# trig3_board_de0-nano_lvds.net
KiCad netlist of a schematic drawn in EAGLE
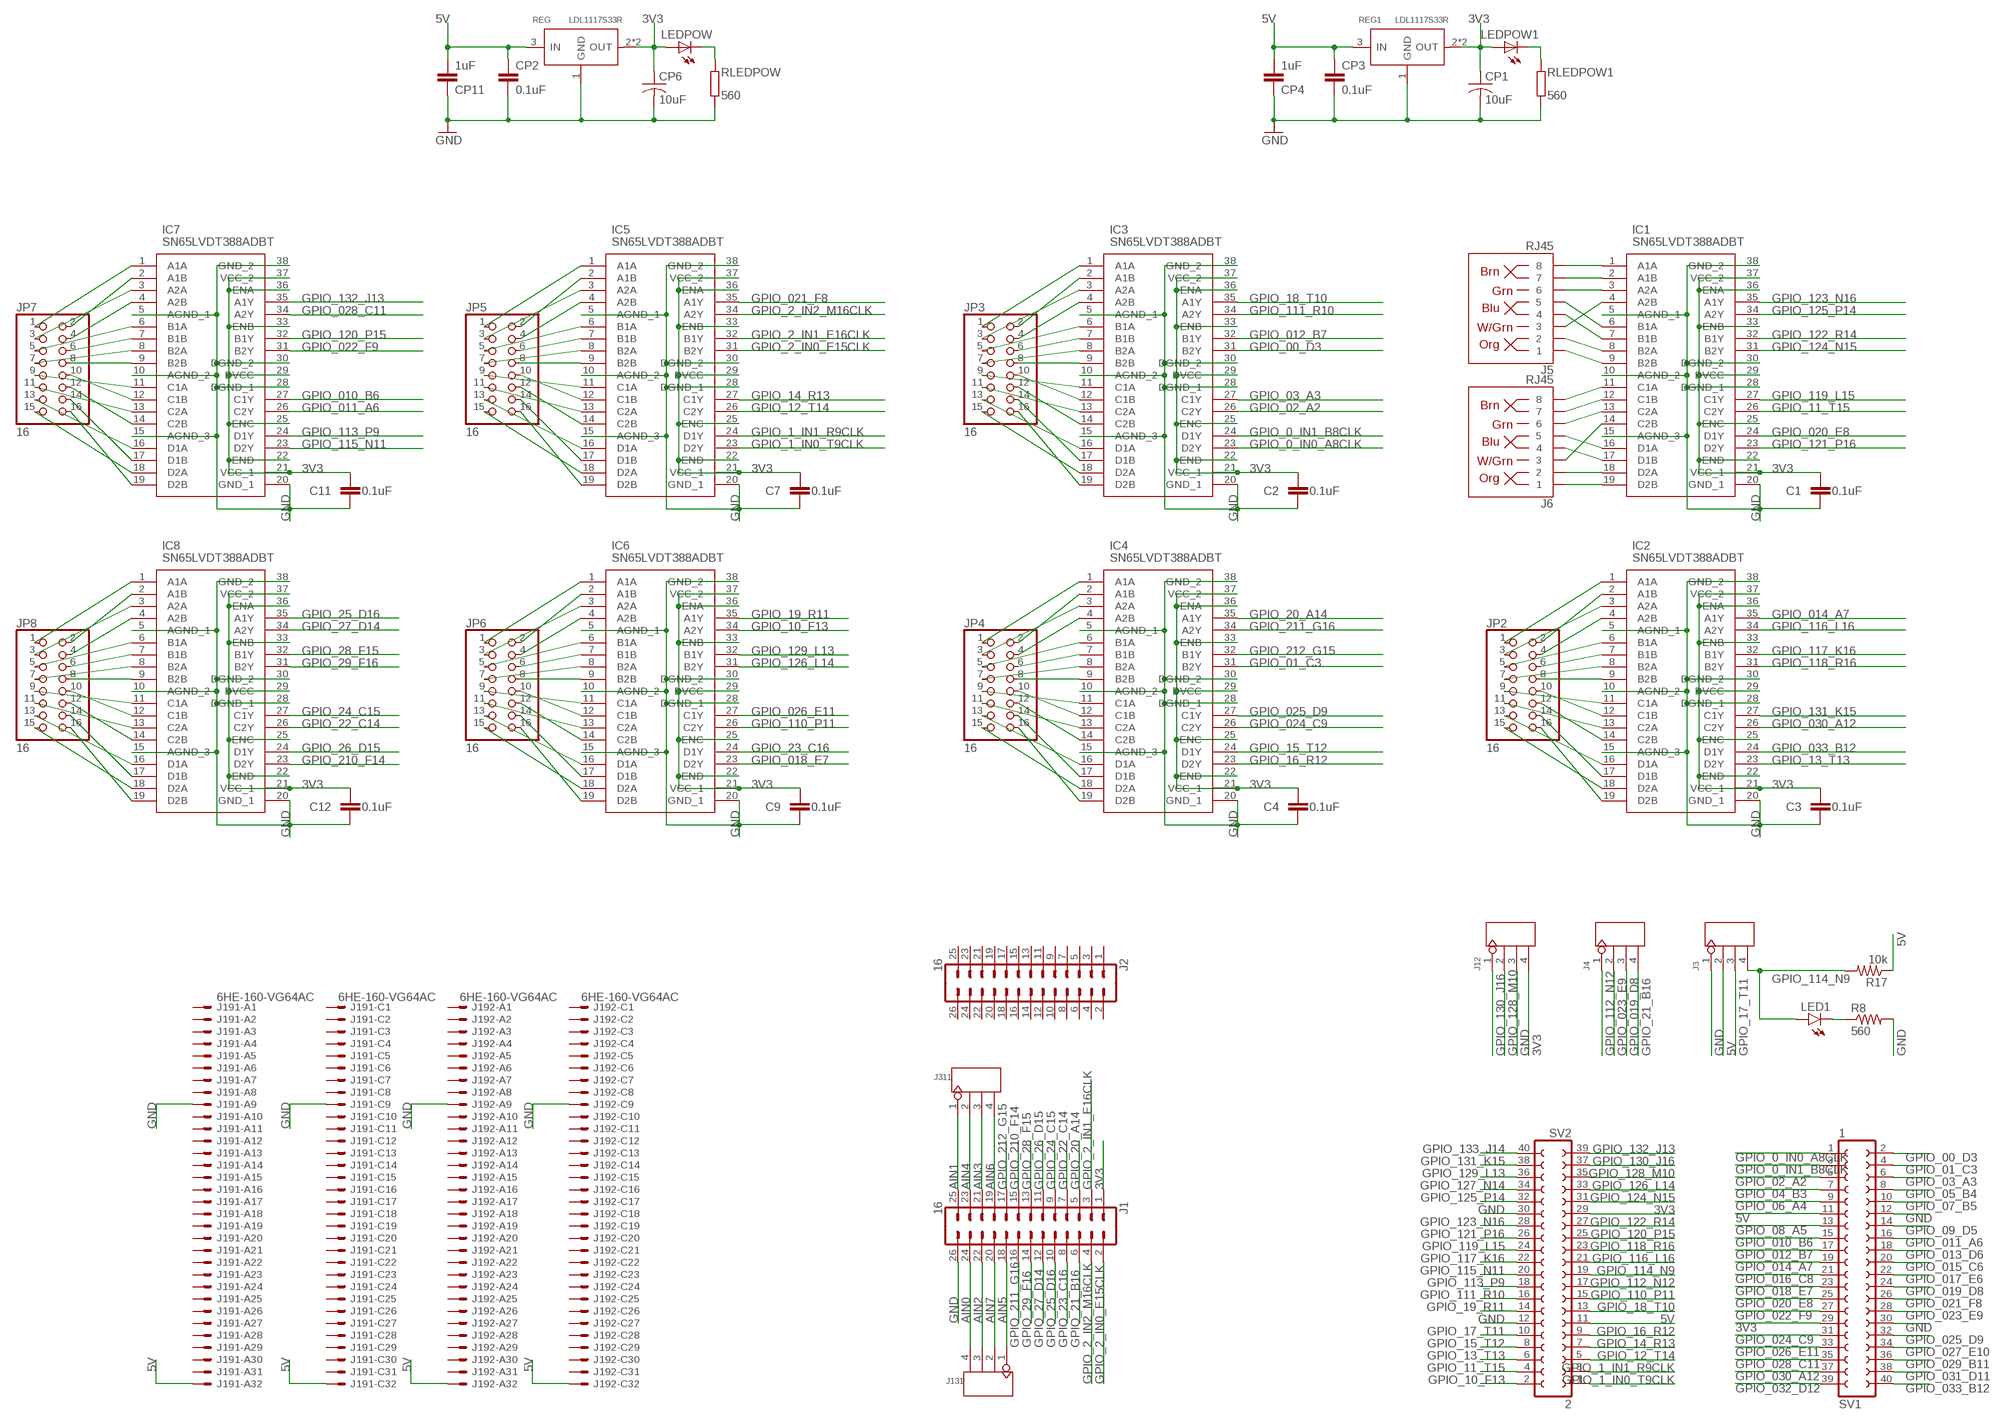
[diagram p0: schematic, sheet 1, part 1 of 2]
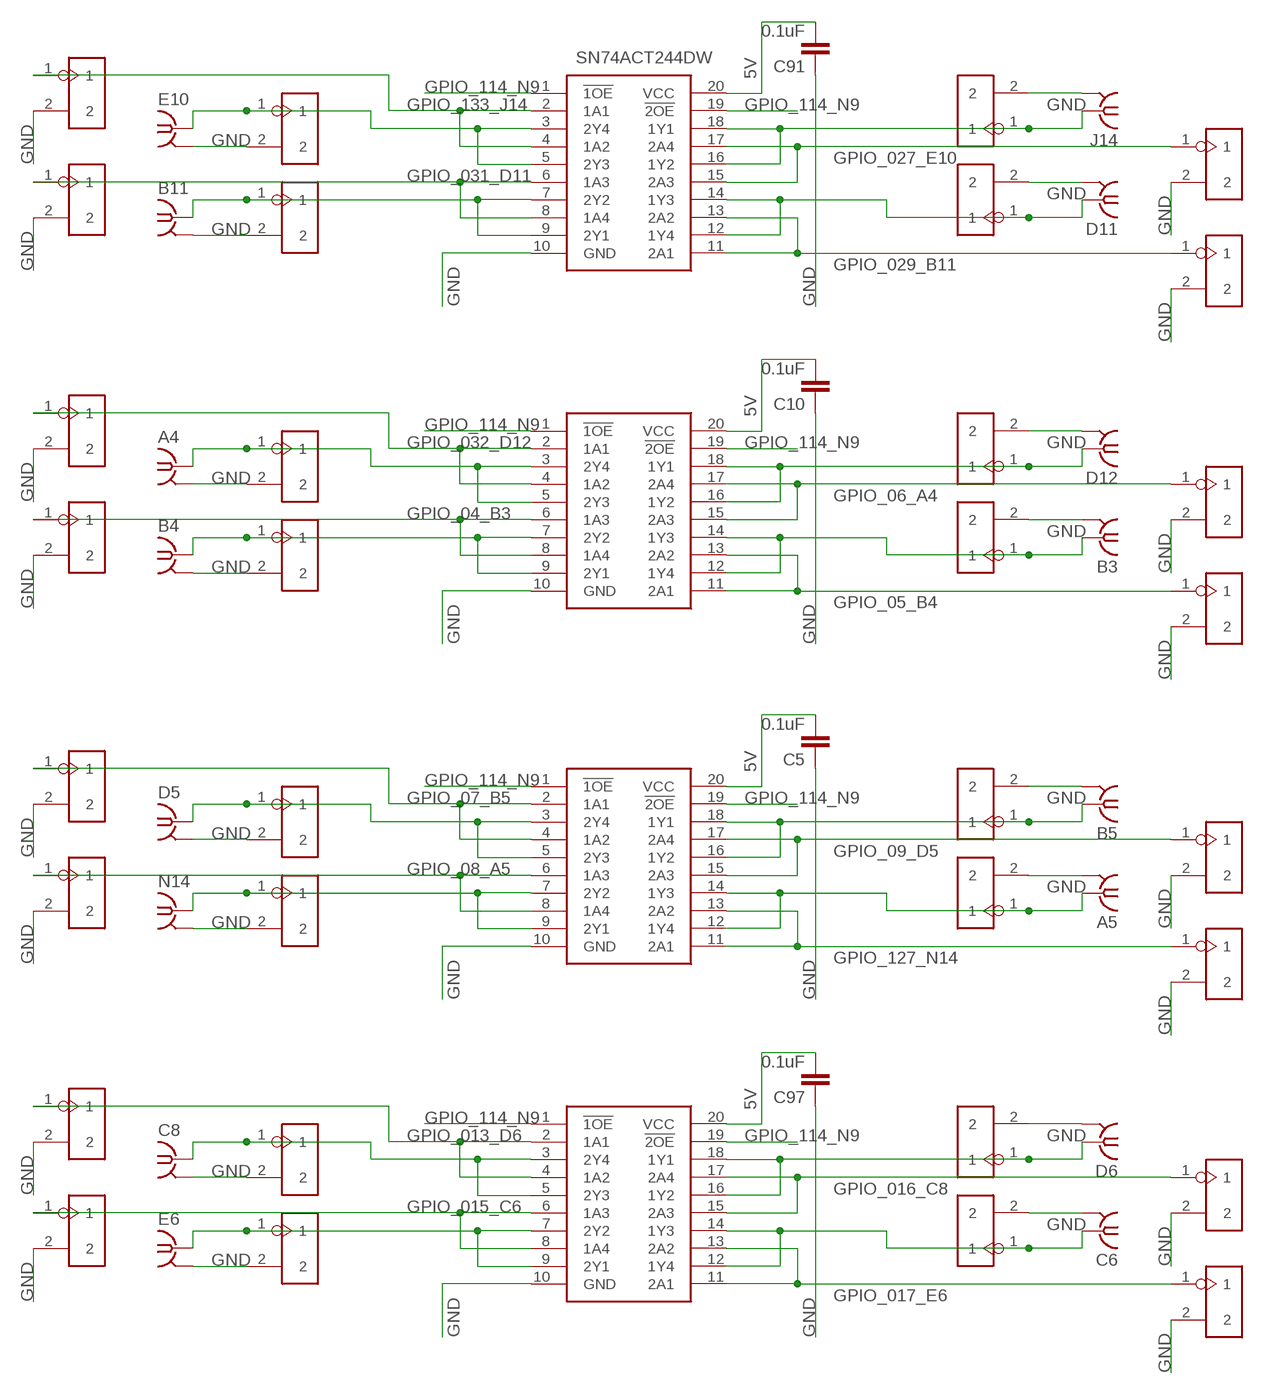
[diagram p1: schematic, sheet 1, part 2 of 2]

(export (version "E")
  (design (tool "Eeschema 10.0.6"))
  (components
    (comp (ref "A4")
      (value "BU-SMB-V")
      (footprint "eagle-import:BU-SMB-V")
      (libsource (lib "eagle-import") (part "BU-SMB-V"))
    )
    (comp (ref "A5")
      (value "BU-SMB-V")
      (footprint "eagle-import:BU-SMB-V")
      (libsource (lib "eagle-import") (part "BU-SMB-V"))
    )
    (comp (ref "B3")
      (value "BU-SMB-V")
      (footprint "eagle-import:BU-SMB-V")
      (libsource (lib "eagle-import") (part "BU-SMB-V"))
    )
    (comp (ref "B4")
      (value "BU-SMB-V")
      (footprint "eagle-import:BU-SMB-V")
      (libsource (lib "eagle-import") (part "BU-SMB-V"))
    )
    (comp (ref "B5")
      (value "BU-SMB-V")
      (footprint "eagle-import:BU-SMB-V")
      (libsource (lib "eagle-import") (part "BU-SMB-V"))
    )
    (comp (ref "B11")
      (value "BU-SMB-V")
      (footprint "eagle-import:BU-SMB-V")
      (libsource (lib "eagle-import") (part "BU-SMB-V"))
    )
    (comp (ref "C1")
      (value "0.1uF")
      (footprint "eagle-import:0805")
      (libsource (lib "eagle-import") (part "CAP0805"))
    )
    (comp (ref "C2")
      (value "0.1uF")
      (footprint "eagle-import:0805")
      (libsource (lib "eagle-import") (part "CAP0805"))
    )
    (comp (ref "C3")
      (value "0.1uF")
      (footprint "eagle-import:0805")
      (libsource (lib "eagle-import") (part "CAP0805"))
    )
    (comp (ref "C4")
      (value "0.1uF")
      (footprint "eagle-import:0805")
      (libsource (lib "eagle-import") (part "CAP0805"))
    )
    (comp (ref "C5")
      (value "0.1uF")
      (footprint "eagle-import:0805")
      (libsource (lib "eagle-import") (part "CAP0805"))
    )
    (comp (ref "C6")
      (value "BU-SMB-V")
      (footprint "eagle-import:BU-SMB-V")
      (libsource (lib "eagle-import") (part "BU-SMB-V"))
    )
    (comp (ref "C7")
      (value "0.1uF")
      (footprint "eagle-import:0805")
      (libsource (lib "eagle-import") (part "CAP0805"))
    )
    (comp (ref "C8")
      (value "BU-SMB-V")
      (footprint "eagle-import:BU-SMB-V")
      (libsource (lib "eagle-import") (part "BU-SMB-V"))
    )
    (comp (ref "C9")
      (value "0.1uF")
      (footprint "eagle-import:0805")
      (libsource (lib "eagle-import") (part "CAP0805"))
    )
    (comp (ref "C10")
      (value "0.1uF")
      (footprint "eagle-import:0805")
      (libsource (lib "eagle-import") (part "CAP0805"))
    )
    (comp (ref "C11")
      (value "0.1uF")
      (footprint "eagle-import:0805")
      (libsource (lib "eagle-import") (part "CAP0805"))
    )
    (comp (ref "C12")
      (value "0.1uF")
      (footprint "eagle-import:0805")
      (libsource (lib "eagle-import") (part "CAP0805"))
    )
    (comp (ref "C91")
      (value "0.1uF")
      (footprint "eagle-import:0805")
      (libsource (lib "eagle-import") (part "CAP0805"))
    )
    (comp (ref "C97")
      (value "0.1uF")
      (footprint "eagle-import:0805")
      (libsource (lib "eagle-import") (part "CAP0805"))
    )
    (comp (ref "CP1")
      (value "10uF")
      (footprint "eagle-import:C1206")
      (fields (field (name "MPN") "MF-CAP-1206-10uF"))
      (libsource (lib "eagle-import") (part "C-USC1206"))
    )
    (comp (ref "CP2")
      (value "0.1uF")
      (footprint "eagle-import:C0805K")
      (fields (field (name "MPN") "MF-CAP-0805-0.1uF"))
      (libsource (lib "eagle-import") (part "C-EUC0805K"))
    )
    (comp (ref "CP3")
      (value "0.1uF")
      (footprint "eagle-import:C0805K")
      (fields (field (name "MPN") "MF-CAP-0805-0.1uF"))
      (libsource (lib "eagle-import") (part "C-EUC0805K"))
    )
    (comp (ref "CP4")
      (value "1uF")
      (footprint "eagle-import:C0805K")
      (fields (field (name "MPN") "MF-CAP-0805-1uF"))
      (libsource (lib "eagle-import") (part "C-EUC0805K"))
    )
    (comp (ref "CP6")
      (value "10uF")
      (footprint "eagle-import:C1206")
      (fields (field (name "MPN") "MF-CAP-1206-10uF"))
      (libsource (lib "eagle-import") (part "C-USC1206"))
    )
    (comp (ref "CP11")
      (value "1uF")
      (footprint "eagle-import:C0805K")
      (fields (field (name "MPN") "MF-CAP-0805-1uF"))
      (libsource (lib "eagle-import") (part "C-EUC0805K"))
    )
    (comp (ref "D5")
      (value "BU-SMB-V")
      (footprint "eagle-import:BU-SMB-V")
      (libsource (lib "eagle-import") (part "BU-SMB-V"))
    )
    (comp (ref "D6")
      (value "BU-SMB-V")
      (footprint "eagle-import:BU-SMB-V")
      (libsource (lib "eagle-import") (part "BU-SMB-V"))
    )
    (comp (ref "D11")
      (value "BU-SMB-V")
      (footprint "eagle-import:BU-SMB-V")
      (libsource (lib "eagle-import") (part "BU-SMB-V"))
    )
    (comp (ref "D12")
      (value "BU-SMB-V")
      (footprint "eagle-import:BU-SMB-V")
      (libsource (lib "eagle-import") (part "BU-SMB-V"))
    )
    (comp (ref "E6")
      (value "BU-SMB-V")
      (footprint "eagle-import:BU-SMB-V")
      (libsource (lib "eagle-import") (part "BU-SMB-V"))
    )
    (comp (ref "E10")
      (value "BU-SMB-V")
      (footprint "eagle-import:BU-SMB-V")
      (libsource (lib "eagle-import") (part "BU-SMB-V"))
    )
    (comp (ref "IC1")
      (value "SN65LVDT388ADBT")
      (footprint "eagle-import:SOP50P640X120-38N")
      (fields (field (name "MOUSER_PART_NUMBER") "595-SN65LVDT388ADBT"))
      (libsource (lib "eagle-import") (part "SN65LVDT388ADBT"))
    )
    (comp (ref "IC2")
      (value "SN65LVDT388ADBT")
      (footprint "eagle-import:SOP50P640X120-38N")
      (fields (field (name "MOUSER_PART_NUMBER") "595-SN65LVDT388ADBT"))
      (libsource (lib "eagle-import") (part "SN65LVDT388ADBT"))
    )
    (comp (ref "IC3")
      (value "SN65LVDT388ADBT")
      (footprint "eagle-import:SOP50P640X120-38N")
      (fields (field (name "MOUSER_PART_NUMBER") "595-SN65LVDT388ADBT"))
      (libsource (lib "eagle-import") (part "SN65LVDT388ADBT"))
    )
    (comp (ref "IC4")
      (value "SN65LVDT388ADBT")
      (footprint "eagle-import:SOP50P640X120-38N")
      (fields (field (name "MOUSER_PART_NUMBER") "595-SN65LVDT388ADBT"))
      (libsource (lib "eagle-import") (part "SN65LVDT388ADBT"))
    )
    (comp (ref "IC5")
      (value "SN65LVDT388ADBT")
      (footprint "eagle-import:SOP50P640X120-38N")
      (fields (field (name "MOUSER_PART_NUMBER") "595-SN65LVDT388ADBT"))
      (libsource (lib "eagle-import") (part "SN65LVDT388ADBT"))
    )
    (comp (ref "IC6")
      (value "SN65LVDT388ADBT")
      (footprint "eagle-import:SOP50P640X120-38N")
      (fields (field (name "MOUSER_PART_NUMBER") "595-SN65LVDT388ADBT"))
      (libsource (lib "eagle-import") (part "SN65LVDT388ADBT"))
    )
    (comp (ref "IC7")
      (value "SN65LVDT388ADBT")
      (footprint "eagle-import:SOP50P640X120-38N")
      (fields (field (name "MOUSER_PART_NUMBER") "595-SN65LVDT388ADBT"))
      (libsource (lib "eagle-import") (part "SN65LVDT388ADBT"))
    )
    (comp (ref "IC8")
      (value "SN65LVDT388ADBT")
      (footprint "eagle-import:SOP50P640X120-38N")
      (fields (field (name "MOUSER_PART_NUMBER") "595-SN65LVDT388ADBT"))
      (libsource (lib "eagle-import") (part "SN65LVDT388ADBT"))
    )
    (comp (ref "J1")
      (value "16")
      (footprint "eagle-import:2X13")
      (libsource (lib "eagle-import") (part "M13X22X13"))
    )
    (comp (ref "J2")
      (value "16")
      (footprint "eagle-import:2X13")
      (libsource (lib "eagle-import") (part "M13X22X13"))
    )
    (comp (ref "J3")
      (value "4p-2.54")
      (footprint "eagle-import:H4-2.54")
      (fields (field (name "MPN") "F185-1104A1BSYA1"))
      (libsource (lib "eagle-import") (part "DIP-BLACK-FEMALE-HEADER-VERT(4P-2.54)"))
    )
    (comp (ref "J4")
      (value "4p-2.54")
      (footprint "eagle-import:H4-2.54")
      (fields (field (name "MPN") "F185-1104A1BSYA1"))
      (libsource (lib "eagle-import") (part "DIP-BLACK-FEMALE-HEADER-VERT(4P-2.54)"))
    )
    (comp (ref "J5")
      (value "RJ45")
      (footprint "eagle-import:RJ45-8")
      (libsource (lib "eagle-import") (part "RJ45-8PTH"))
    )
    (comp (ref "J6")
      (value "RJ45")
      (footprint "eagle-import:RJ45-8")
      (libsource (lib "eagle-import") (part "RJ45-8PTH"))
    )
    (comp (ref "J12")
      (value "4p-2.54")
      (footprint "eagle-import:H4-2.54")
      (fields (field (name "MPN") "F185-1104A1BSYA1"))
      (libsource (lib "eagle-import") (part "DIP-BLACK-FEMALE-HEADER-VERT(4P-2.54)"))
    )
    (comp (ref "J14")
      (value "BU-SMB-V")
      (footprint "eagle-import:BU-SMB-V")
      (libsource (lib "eagle-import") (part "BU-SMB-V"))
    )
    (comp (ref "J19")
      (value "6HE-160-VG64AC")
      (footprint "eagle-import:6HE_160-VG64AC")
      (libsource (lib "eagle-import") (part "6HE-?-VG64AC160"))
    )
    (comp (ref "J131")
      (value "4p-2.54")
      (footprint "eagle-import:H4-2.54")
      (fields (field (name "MPN") "F185-1104A1BSYA1"))
      (libsource (lib "eagle-import") (part "DIP-BLACK-FEMALE-HEADER-VERT(4P-2.54)"))
    )
    (comp (ref "J311")
      (value "4p-2.54")
      (footprint "eagle-import:H4-2.54")
      (fields (field (name "MPN") "F185-1104A1BSYA1"))
      (libsource (lib "eagle-import") (part "DIP-BLACK-FEMALE-HEADER-VERT(4P-2.54)"))
    )
    (comp (ref "JP2")
      (value "16")
      (footprint "eagle-import:2X08_90")
      (libsource (lib "eagle-import") (part "PINHD-2X8/90"))
    )
    (comp (ref "JP3")
      (value "16")
      (footprint "eagle-import:2X08_90")
      (libsource (lib "eagle-import") (part "PINHD-2X8/90"))
    )
    (comp (ref "JP4")
      (value "16")
      (footprint "eagle-import:2X08_90")
      (libsource (lib "eagle-import") (part "PINHD-2X8/90"))
    )
    (comp (ref "JP5")
      (value "16")
      (footprint "eagle-import:2X08_90")
      (libsource (lib "eagle-import") (part "PINHD-2X8/90"))
    )
    (comp (ref "JP6")
      (value "16")
      (footprint "eagle-import:2X08_90")
      (libsource (lib "eagle-import") (part "PINHD-2X8/90"))
    )
    (comp (ref "JP7")
      (value "16")
      (footprint "eagle-import:2X08_90")
      (libsource (lib "eagle-import") (part "PINHD-2X8/90"))
    )
    (comp (ref "JP8")
      (value "16")
      (footprint "eagle-import:2X08_90")
      (libsource (lib "eagle-import") (part "PINHD-2X8/90"))
    )
    (comp (ref "LED1")
      (value "red")
      (footprint "eagle-import:CHIP-LED0805")
      (libsource (lib "eagle-import") (part "led_259_LEDCHIP-LED0805"))
    )
    (comp (ref "LEDPOW")
      (value "MF-LED-0805-RED")
      (footprint "eagle-import:SML0805")
      (libsource (lib "eagle-import") (part "LEDSML0805"))
    )
    (comp (ref "LEDPOW1")
      (value "MF-LED-0805-RED")
      (footprint "eagle-import:SML0805")
      (libsource (lib "eagle-import") (part "LEDSML0805"))
    )
    (comp (ref "N14")
      (value "BU-SMB-V")
      (footprint "eagle-import:BU-SMB-V")
      (libsource (lib "eagle-import") (part "BU-SMB-V"))
    )
    (comp (ref "OJ1")
      (value "2p-2.54")
      (footprint "eagle-import:H2-2.54")
      (fields (field (name "MPN") "P125-1102A0BS116A1"))
      (libsource (lib "eagle-import") (part "DIP-BLACK-MALE-HEADER-VERT(2P-2.54)"))
    )
    (comp (ref "OJ2")
      (value "2p-2.54")
      (footprint "eagle-import:H2-2.54")
      (fields (field (name "MPN") "P125-1102A0BS116A1"))
      (libsource (lib "eagle-import") (part "DIP-BLACK-MALE-HEADER-VERT(2P-2.54)"))
    )
    (comp (ref "OJ3")
      (value "2p-2.54")
      (footprint "eagle-import:H2-2.54")
      (fields (field (name "MPN") "P125-1102A0BS116A1"))
      (libsource (lib "eagle-import") (part "DIP-BLACK-MALE-HEADER-VERT(2P-2.54)"))
    )
    (comp (ref "OJ4")
      (value "2p-2.54")
      (footprint "eagle-import:H2-2.54")
      (fields (field (name "MPN") "P125-1102A0BS116A1"))
      (libsource (lib "eagle-import") (part "DIP-BLACK-MALE-HEADER-VERT(2P-2.54)"))
    )
    (comp (ref "OJ5")
      (value "2p-2.54")
      (footprint "eagle-import:H2-2.54")
      (fields (field (name "MPN") "P125-1102A0BS116A1"))
      (libsource (lib "eagle-import") (part "DIP-BLACK-MALE-HEADER-VERT(2P-2.54)"))
    )
    (comp (ref "OJ6")
      (value "2p-2.54")
      (footprint "eagle-import:H2-2.54")
      (fields (field (name "MPN") "P125-1102A0BS116A1"))
      (libsource (lib "eagle-import") (part "DIP-BLACK-MALE-HEADER-VERT(2P-2.54)"))
    )
    (comp (ref "OJ7")
      (value "2p-2.54")
      (footprint "eagle-import:H2-2.54")
      (fields (field (name "MPN") "P125-1102A0BS116A1"))
      (libsource (lib "eagle-import") (part "DIP-BLACK-MALE-HEADER-VERT(2P-2.54)"))
    )
    (comp (ref "OJ8")
      (value "2p-2.54")
      (footprint "eagle-import:H2-2.54")
      (fields (field (name "MPN") "P125-1102A0BS116A1"))
      (libsource (lib "eagle-import") (part "DIP-BLACK-MALE-HEADER-VERT(2P-2.54)"))
    )
    (comp (ref "OJ49")
      (value "2p-2.54")
      (footprint "eagle-import:H2-2.54")
      (fields (field (name "MPN") "P125-1102A0BS116A1"))
      (libsource (lib "eagle-import") (part "DIP-BLACK-MALE-HEADER-VERT(2P-2.54)"))
    )
    (comp (ref "OJ50")
      (value "2p-2.54")
      (footprint "eagle-import:H2-2.54")
      (fields (field (name "MPN") "P125-1102A0BS116A1"))
      (libsource (lib "eagle-import") (part "DIP-BLACK-MALE-HEADER-VERT(2P-2.54)"))
    )
    (comp (ref "OJ51")
      (value "2p-2.54")
      (footprint "eagle-import:H2-2.54")
      (fields (field (name "MPN") "P125-1102A0BS116A1"))
      (libsource (lib "eagle-import") (part "DIP-BLACK-MALE-HEADER-VERT(2P-2.54)"))
    )
    (comp (ref "OJ52")
      (value "2p-2.54")
      (footprint "eagle-import:H2-2.54")
      (fields (field (name "MPN") "P125-1102A0BS116A1"))
      (libsource (lib "eagle-import") (part "DIP-BLACK-MALE-HEADER-VERT(2P-2.54)"))
    )
    (comp (ref "OJ53")
      (value "2p-2.54")
      (footprint "eagle-import:H2-2.54")
      (fields (field (name "MPN") "P125-1102A0BS116A1"))
      (libsource (lib "eagle-import") (part "DIP-BLACK-MALE-HEADER-VERT(2P-2.54)"))
    )
    (comp (ref "OJ54")
      (value "2p-2.54")
      (footprint "eagle-import:H2-2.54")
      (fields (field (name "MPN") "P125-1102A0BS116A1"))
      (libsource (lib "eagle-import") (part "DIP-BLACK-MALE-HEADER-VERT(2P-2.54)"))
    )
    (comp (ref "OJ55")
      (value "2p-2.54")
      (footprint "eagle-import:H2-2.54")
      (fields (field (name "MPN") "P125-1102A0BS116A1"))
      (libsource (lib "eagle-import") (part "DIP-BLACK-MALE-HEADER-VERT(2P-2.54)"))
    )
    (comp (ref "OJ56")
      (value "2p-2.54")
      (footprint "eagle-import:H2-2.54")
      (fields (field (name "MPN") "P125-1102A0BS116A1"))
      (libsource (lib "eagle-import") (part "DIP-BLACK-MALE-HEADER-VERT(2P-2.54)"))
    )
    (comp (ref "OJ65")
      (value "2p-2.54")
      (footprint "eagle-import:H2-2.54")
      (fields (field (name "MPN") "P125-1102A0BS116A1"))
      (libsource (lib "eagle-import") (part "DIP-BLACK-MALE-HEADER-VERT(2P-2.54)"))
    )
    (comp (ref "OJ66")
      (value "2p-2.54")
      (footprint "eagle-import:H2-2.54")
      (fields (field (name "MPN") "P125-1102A0BS116A1"))
      (libsource (lib "eagle-import") (part "DIP-BLACK-MALE-HEADER-VERT(2P-2.54)"))
    )
    (comp (ref "OJ67")
      (value "2p-2.54")
      (footprint "eagle-import:H2-2.54")
      (fields (field (name "MPN") "P125-1102A0BS116A1"))
      (libsource (lib "eagle-import") (part "DIP-BLACK-MALE-HEADER-VERT(2P-2.54)"))
    )
    (comp (ref "OJ68")
      (value "2p-2.54")
      (footprint "eagle-import:H2-2.54")
      (fields (field (name "MPN") "P125-1102A0BS116A1"))
      (libsource (lib "eagle-import") (part "DIP-BLACK-MALE-HEADER-VERT(2P-2.54)"))
    )
    (comp (ref "OJ69")
      (value "2p-2.54")
      (footprint "eagle-import:H2-2.54")
      (fields (field (name "MPN") "P125-1102A0BS116A1"))
      (libsource (lib "eagle-import") (part "DIP-BLACK-MALE-HEADER-VERT(2P-2.54)"))
    )
    (comp (ref "OJ70")
      (value "2p-2.54")
      (footprint "eagle-import:H2-2.54")
      (fields (field (name "MPN") "P125-1102A0BS116A1"))
      (libsource (lib "eagle-import") (part "DIP-BLACK-MALE-HEADER-VERT(2P-2.54)"))
    )
    (comp (ref "OJ71")
      (value "2p-2.54")
      (footprint "eagle-import:H2-2.54")
      (fields (field (name "MPN") "P125-1102A0BS116A1"))
      (libsource (lib "eagle-import") (part "DIP-BLACK-MALE-HEADER-VERT(2P-2.54)"))
    )
    (comp (ref "OJ72")
      (value "2p-2.54")
      (footprint "eagle-import:H2-2.54")
      (fields (field (name "MPN") "P125-1102A0BS116A1"))
      (libsource (lib "eagle-import") (part "DIP-BLACK-MALE-HEADER-VERT(2P-2.54)"))
    )
    (comp (ref "OJ89")
      (value "2p-2.54")
      (footprint "eagle-import:H2-2.54")
      (fields (field (name "MPN") "P125-1102A0BS116A1"))
      (libsource (lib "eagle-import") (part "DIP-BLACK-MALE-HEADER-VERT(2P-2.54)"))
    )
    (comp (ref "OJ90")
      (value "2p-2.54")
      (footprint "eagle-import:H2-2.54")
      (fields (field (name "MPN") "P125-1102A0BS116A1"))
      (libsource (lib "eagle-import") (part "DIP-BLACK-MALE-HEADER-VERT(2P-2.54)"))
    )
    (comp (ref "OJ91")
      (value "2p-2.54")
      (footprint "eagle-import:H2-2.54")
      (fields (field (name "MPN") "P125-1102A0BS116A1"))
      (libsource (lib "eagle-import") (part "DIP-BLACK-MALE-HEADER-VERT(2P-2.54)"))
    )
    (comp (ref "OJ92")
      (value "2p-2.54")
      (footprint "eagle-import:H2-2.54")
      (fields (field (name "MPN") "P125-1102A0BS116A1"))
      (libsource (lib "eagle-import") (part "DIP-BLACK-MALE-HEADER-VERT(2P-2.54)"))
    )
    (comp (ref "OJ93")
      (value "2p-2.54")
      (footprint "eagle-import:H2-2.54")
      (fields (field (name "MPN") "P125-1102A0BS116A1"))
      (libsource (lib "eagle-import") (part "DIP-BLACK-MALE-HEADER-VERT(2P-2.54)"))
    )
    (comp (ref "OJ94")
      (value "2p-2.54")
      (footprint "eagle-import:H2-2.54")
      (fields (field (name "MPN") "P125-1102A0BS116A1"))
      (libsource (lib "eagle-import") (part "DIP-BLACK-MALE-HEADER-VERT(2P-2.54)"))
    )
    (comp (ref "OJ95")
      (value "2p-2.54")
      (footprint "eagle-import:H2-2.54")
      (fields (field (name "MPN") "P125-1102A0BS116A1"))
      (libsource (lib "eagle-import") (part "DIP-BLACK-MALE-HEADER-VERT(2P-2.54)"))
    )
    (comp (ref "OJ96")
      (value "2p-2.54")
      (footprint "eagle-import:H2-2.54")
      (fields (field (name "MPN") "P125-1102A0BS116A1"))
      (libsource (lib "eagle-import") (part "DIP-BLACK-MALE-HEADER-VERT(2P-2.54)"))
    )
    (comp (ref "R8")
      (value "560")
      (footprint "eagle-import:R0805")
      (libsource (lib "eagle-import") (part "R-US_R0805"))
    )
    (comp (ref "R17")
      (value "10k")
      (footprint "eagle-import:AXIAL-0.3")
      (libsource (lib "eagle-import") (part "RESISTORAXIAL-0.3"))
    )
    (comp (ref "REG")
      (value "LDL1117S33R")
      (footprint "eagle-import:SOT-223")
      (fields (field (name "MPN") "CJT1117-3.3") (field (name "MPN_1") "LDL1117S33R"))
      (libsource (lib "eagle-import") (part "PMIC-CJT1117-3.3(SOT223)"))
    )
    (comp (ref "REG1")
      (value "LDL1117S33R")
      (footprint "eagle-import:SOT-223")
      (fields (field (name "MPN") "CJT1117-3.3") (field (name "MPN_1") "LDL1117S33R"))
      (libsource (lib "eagle-import") (part "PMIC-CJT1117-3.3(SOT223)"))
    )
    (comp (ref "RLEDPOW")
      (value "560")
      (footprint "eagle-import:R0805")
      (fields (field (name "MPN") "MF-RES-0805-560"))
      (libsource (lib "eagle-import") (part "R-EU_R0805"))
    )
    (comp (ref "RLEDPOW1")
      (value "560")
      (footprint "eagle-import:R0805")
      (fields (field (name "MPN") "MF-RES-0805-560"))
      (libsource (lib "eagle-import") (part "R-EU_R0805"))
    )
    (comp (ref "SV1")
      (value "1")
      (footprint "eagle-import:FE20-2")
      (libsource (lib "eagle-import") (part "FE20-2"))
    )
    (comp (ref "SV2")
      (value "2")
      (footprint "eagle-import:FE20-2")
      (libsource (lib "eagle-import") (part "FE20-2"))
    )
    (comp (ref "VSLUE")
      (value "SN74ACT244DW")
      (footprint "eagle-import:SOIC127P1030X265-20N")
      (fields (field (name "RS_PART_NUMBER") "4363169"))
      (libsource (lib "eagle-import") (part "SN74ACT244DW"))
    )
    (comp (ref "VSLUE6")
      (value "SN74ACT244DW")
      (footprint "eagle-import:SOIC127P1030X265-20N")
      (fields (field (name "RS_PART_NUMBER") "4363169"))
      (libsource (lib "eagle-import") (part "SN74ACT244DW"))
    )
    (comp (ref "VSLUE8")
      (value "SN74ACT244DW")
      (footprint "eagle-import:SOIC127P1030X265-20N")
      (fields (field (name "RS_PART_NUMBER") "4363169"))
      (libsource (lib "eagle-import") (part "SN74ACT244DW"))
    )
    (comp (ref "VSLUE11")
      (value "SN74ACT244DW")
      (footprint "eagle-import:SOIC127P1030X265-20N")
      (fields (field (name "RS_PART_NUMBER") "4363169"))
      (libsource (lib "eagle-import") (part "SN74ACT244DW"))
    )
  )
  (nets
    (net (code "1") (name "/3V3") (class "Default")
      (node (ref "C1") (pin "2") (pinfunction "2_2") (pintype "passive"))
      (node (ref "C11") (pin "2") (pinfunction "2_2") (pintype "passive"))
      (node (ref "C12") (pin "2") (pinfunction "2_2") (pintype "passive"))
      (node (ref "C2") (pin "2") (pinfunction "2_2") (pintype "passive"))
      (node (ref "C3") (pin "2") (pinfunction "2_2") (pintype "passive"))
      (node (ref "C4") (pin "2") (pinfunction "2_2") (pintype "passive"))
      (node (ref "C7") (pin "2") (pinfunction "2_2") (pintype "passive"))
      (node (ref "C9") (pin "2") (pinfunction "2_2") (pintype "passive"))
      (node (ref "CP1") (pin "1") (pinfunction "1_1") (pintype "passive"))
      (node (ref "CP6") (pin "1") (pinfunction "1_1") (pintype "passive"))
      (node (ref "IC1") (pin "21") (pinfunction "VCC_1_21") (pintype "bidirectional"))
      (node (ref "IC1") (pin "22") (pinfunction "END_22") (pintype "bidirectional"))
      (node (ref "IC1") (pin "25") (pinfunction "ENC_25") (pintype "bidirectional"))
      (node (ref "IC1") (pin "29") (pinfunction "DVCC_29") (pintype "bidirectional"))
      (node (ref "IC1") (pin "33") (pinfunction "ENB_33") (pintype "bidirectional"))
      (node (ref "IC1") (pin "36") (pinfunction "ENA_36") (pintype "bidirectional"))
      (node (ref "IC1") (pin "37") (pinfunction "VCC_2_37") (pintype "bidirectional"))
      (node (ref "IC2") (pin "21") (pinfunction "VCC_1_21") (pintype "bidirectional"))
      (node (ref "IC2") (pin "22") (pinfunction "END_22") (pintype "bidirectional"))
      (node (ref "IC2") (pin "25") (pinfunction "ENC_25") (pintype "bidirectional"))
      (node (ref "IC2") (pin "29") (pinfunction "DVCC_29") (pintype "bidirectional"))
      (node (ref "IC2") (pin "33") (pinfunction "ENB_33") (pintype "bidirectional"))
      (node (ref "IC2") (pin "36") (pinfunction "ENA_36") (pintype "bidirectional"))
      (node (ref "IC2") (pin "37") (pinfunction "VCC_2_37") (pintype "bidirectional"))
      (node (ref "IC3") (pin "21") (pinfunction "VCC_1_21") (pintype "bidirectional"))
      (node (ref "IC3") (pin "22") (pinfunction "END_22") (pintype "bidirectional"))
      (node (ref "IC3") (pin "25") (pinfunction "ENC_25") (pintype "bidirectional"))
      (node (ref "IC3") (pin "29") (pinfunction "DVCC_29") (pintype "bidirectional"))
      (node (ref "IC3") (pin "33") (pinfunction "ENB_33") (pintype "bidirectional"))
      (node (ref "IC3") (pin "36") (pinfunction "ENA_36") (pintype "bidirectional"))
      (node (ref "IC3") (pin "37") (pinfunction "VCC_2_37") (pintype "bidirectional"))
      (node (ref "IC4") (pin "21") (pinfunction "VCC_1_21") (pintype "bidirectional"))
      (node (ref "IC4") (pin "22") (pinfunction "END_22") (pintype "bidirectional"))
      (node (ref "IC4") (pin "25") (pinfunction "ENC_25") (pintype "bidirectional"))
      (node (ref "IC4") (pin "29") (pinfunction "DVCC_29") (pintype "bidirectional"))
      (node (ref "IC4") (pin "33") (pinfunction "ENB_33") (pintype "bidirectional"))
      (node (ref "IC4") (pin "36") (pinfunction "ENA_36") (pintype "bidirectional"))
      (node (ref "IC4") (pin "37") (pinfunction "VCC_2_37") (pintype "bidirectional"))
      (node (ref "IC5") (pin "21") (pinfunction "VCC_1_21") (pintype "bidirectional"))
      (node (ref "IC5") (pin "22") (pinfunction "END_22") (pintype "bidirectional"))
      (node (ref "IC5") (pin "25") (pinfunction "ENC_25") (pintype "bidirectional"))
      (node (ref "IC5") (pin "29") (pinfunction "DVCC_29") (pintype "bidirectional"))
      (node (ref "IC5") (pin "33") (pinfunction "ENB_33") (pintype "bidirectional"))
      (node (ref "IC5") (pin "36") (pinfunction "ENA_36") (pintype "bidirectional"))
      (node (ref "IC5") (pin "37") (pinfunction "VCC_2_37") (pintype "bidirectional"))
      (node (ref "IC6") (pin "21") (pinfunction "VCC_1_21") (pintype "bidirectional"))
      (node (ref "IC6") (pin "22") (pinfunction "END_22") (pintype "bidirectional"))
      (node (ref "IC6") (pin "25") (pinfunction "ENC_25") (pintype "bidirectional"))
      (node (ref "IC6") (pin "29") (pinfunction "DVCC_29") (pintype "bidirectional"))
      (node (ref "IC6") (pin "33") (pinfunction "ENB_33") (pintype "bidirectional"))
      (node (ref "IC6") (pin "36") (pinfunction "ENA_36") (pintype "bidirectional"))
      (node (ref "IC6") (pin "37") (pinfunction "VCC_2_37") (pintype "bidirectional"))
      (node (ref "IC7") (pin "21") (pinfunction "VCC_1_21") (pintype "bidirectional"))
      (node (ref "IC7") (pin "22") (pinfunction "END_22") (pintype "bidirectional"))
      (node (ref "IC7") (pin "25") (pinfunction "ENC_25") (pintype "bidirectional"))
      (node (ref "IC7") (pin "29") (pinfunction "DVCC_29") (pintype "bidirectional"))
      (node (ref "IC7") (pin "33") (pinfunction "ENB_33") (pintype "bidirectional"))
      (node (ref "IC7") (pin "36") (pinfunction "ENA_36") (pintype "bidirectional"))
      (node (ref "IC7") (pin "37") (pinfunction "VCC_2_37") (pintype "bidirectional"))
      (node (ref "IC8") (pin "21") (pinfunction "VCC_1_21") (pintype "bidirectional"))
      (node (ref "IC8") (pin "22") (pinfunction "END_22") (pintype "bidirectional"))
      (node (ref "IC8") (pin "25") (pinfunction "ENC_25") (pintype "bidirectional"))
      (node (ref "IC8") (pin "29") (pinfunction "DVCC_29") (pintype "bidirectional"))
      (node (ref "IC8") (pin "33") (pinfunction "ENB_33") (pintype "bidirectional"))
      (node (ref "IC8") (pin "36") (pinfunction "ENA_36") (pintype "bidirectional"))
      (node (ref "IC8") (pin "37") (pinfunction "VCC_2_37") (pintype "bidirectional"))
      (node (ref "J1") (pin "1") (pinfunction "1_1") (pintype "passive"))
      (node (ref "J12") (pin "4") (pinfunction "P$4_4") (pintype "bidirectional"))
      (node (ref "LEDPOW") (pin "A") (pinfunction "A_A") (pintype "passive"))
      (node (ref "LEDPOW1") (pin "A") (pinfunction "A_A") (pintype "passive"))
      (node (ref "REG") (pin "2") (pinfunction "OUT_2") (pintype "bidirectional"))
      (node (ref "REG") (pin "TER") (pinfunction "OUT_TER") (pintype "bidirectional"))
      (node (ref "REG1") (pin "2") (pinfunction "OUT_2") (pintype "bidirectional"))
      (node (ref "REG1") (pin "TER") (pinfunction "OUT_TER") (pintype "bidirectional"))
      (node (ref "SV1") (pin "29") (pinfunction "29_29") (pintype "passive"))
      (node (ref "SV2") (pin "29") (pinfunction "29_29") (pintype "passive"))
    )
    (net (code "2") (name "/5V") (class "Default")
      (node (ref "C10") (pin "2") (pinfunction "2_2") (pintype "passive"))
      (node (ref "C5") (pin "2") (pinfunction "2_2") (pintype "passive"))
      (node (ref "C91") (pin "2") (pinfunction "2_2") (pintype "passive"))
      (node (ref "C97") (pin "2") (pinfunction "2_2") (pintype "passive"))
      (node (ref "CP11") (pin "2") (pinfunction "2_2") (pintype "passive"))
      (node (ref "CP2") (pin "1") (pinfunction "1_1") (pintype "passive"))
      (node (ref "CP3") (pin "1") (pinfunction "1_1") (pintype "passive"))
      (node (ref "CP4") (pin "2") (pinfunction "2_2") (pintype "passive"))
      (node (ref "J19") (pin "1-A32") (pinfunction "MS_1-A32") (pintype "passive"))
      (node (ref "J19") (pin "1-C32") (pinfunction "MS_1-C32") (pintype "passive"))
      (node (ref "J19") (pin "2-A32") (pinfunction "MS_2-A32") (pintype "passive"))
      (node (ref "J19") (pin "2-C32") (pinfunction "MS_2-C32") (pintype "passive"))
      (node (ref "J3") (pin "2") (pinfunction "P$2_2") (pintype "bidirectional"))
      (node (ref "R17") (pin "P$1") (pinfunction "1_P$1") (pintype "passive"))
      (node (ref "REG") (pin "3") (pinfunction "IN_3") (pintype "bidirectional"))
      (node (ref "REG1") (pin "3") (pinfunction "IN_3") (pintype "bidirectional"))
      (node (ref "SV1") (pin "11") (pinfunction "11_11") (pintype "passive"))
      (node (ref "SV2") (pin "11") (pinfunction "11_11") (pintype "passive"))
      (node (ref "VSLUE") (pin "20") (pinfunction "VCC_20") (pintype "power_in"))
      (node (ref "VSLUE11") (pin "20") (pinfunction "VCC_20") (pintype "power_in"))
      (node (ref "VSLUE6") (pin "20") (pinfunction "VCC_20") (pintype "power_in"))
      (node (ref "VSLUE8") (pin "20") (pinfunction "VCC_20") (pintype "power_in"))
    )
    (net (code "3") (name "/AIN0") (class "Default")
      (node (ref "J1") (pin "24") (pinfunction "24_24") (pintype "passive"))
      (node (ref "J131") (pin "4") (pinfunction "P$4_4") (pintype "bidirectional"))
    )
    (net (code "4") (name "/AIN1") (class "Default")
      (node (ref "J1") (pin "25") (pinfunction "25_25") (pintype "passive"))
      (node (ref "J311") (pin "1") (pinfunction "P$1_1") (pintype "bidirectional"))
    )
    (net (code "5") (name "/AIN2") (class "Default")
      (node (ref "J1") (pin "22") (pinfunction "22_22") (pintype "passive"))
      (node (ref "J131") (pin "3") (pinfunction "P$3_3") (pintype "bidirectional"))
    )
    (net (code "6") (name "/AIN3") (class "Default")
      (node (ref "J1") (pin "21") (pinfunction "21_21") (pintype "passive"))
      (node (ref "J311") (pin "3") (pinfunction "P$3_3") (pintype "bidirectional"))
    )
    (net (code "7") (name "/AIN4") (class "Default")
      (node (ref "J1") (pin "23") (pinfunction "23_23") (pintype "passive"))
      (node (ref "J311") (pin "2") (pinfunction "P$2_2") (pintype "bidirectional"))
    )
    (net (code "8") (name "/AIN5") (class "Default")
      (node (ref "J1") (pin "18") (pinfunction "18_18") (pintype "passive"))
      (node (ref "J131") (pin "1") (pinfunction "P$1_1") (pintype "bidirectional"))
    )
    (net (code "9") (name "/AIN6") (class "Default")
      (node (ref "J1") (pin "19") (pinfunction "19_19") (pintype "passive"))
      (node (ref "J311") (pin "4") (pinfunction "P$4_4") (pintype "bidirectional"))
    )
    (net (code "10") (name "/AIN7") (class "Default")
      (node (ref "J1") (pin "20") (pinfunction "20_20") (pintype "passive"))
      (node (ref "J131") (pin "2") (pinfunction "P$2_2") (pintype "bidirectional"))
    )
    (net (code "11") (name "/GPIO_00_D3") (class "Default")
      (node (ref "IC3") (pin "31") (pinfunction "B2Y_31") (pintype "bidirectional"))
      (node (ref "SV1") (pin "2") (pinfunction "2_2") (pintype "passive"))
    )
    (net (code "12") (name "/GPIO_0_IN0_A8CLK") (class "Default")
      (node (ref "IC3") (pin "23") (pinfunction "D2Y_23") (pintype "bidirectional"))
      (node (ref "SV1") (pin "1") (pinfunction "1_1") (pintype "passive"))
    )
    (net (code "13") (name "/GPIO_0_IN1_B8CLK") (class "Default")
      (node (ref "IC3") (pin "24") (pinfunction "D1Y_24") (pintype "bidirectional"))
      (node (ref "SV1") (pin "3") (pinfunction "3_3") (pintype "passive"))
    )
    (net (code "14") (name "/GPIO_01_C3") (class "Default")
      (node (ref "IC4") (pin "31") (pinfunction "B2Y_31") (pintype "bidirectional"))
      (node (ref "SV1") (pin "4") (pinfunction "4_4") (pintype "passive"))
    )
    (net (code "15") (name "/GPIO_1_IN0_T9CLK") (class "Default")
      (node (ref "IC5") (pin "23") (pinfunction "D2Y_23") (pintype "bidirectional"))
      (node (ref "SV2") (pin "1") (pinfunction "1_1") (pintype "passive"))
    )
    (net (code "16") (name "/GPIO_1_IN1_R9CLK") (class "Default")
      (node (ref "IC5") (pin "24") (pinfunction "D1Y_24") (pintype "bidirectional"))
      (node (ref "SV2") (pin "3") (pinfunction "3_3") (pintype "passive"))
    )
    (net (code "17") (name "/GPIO_02_A2") (class "Default")
      (node (ref "IC3") (pin "26") (pinfunction "C2Y_26") (pintype "bidirectional"))
      (node (ref "SV1") (pin "5") (pinfunction "5_5") (pintype "passive"))
    )
    (net (code "18") (name "/GPIO_2_IN0_E15CLK") (class "Default")
      (node (ref "IC5") (pin "31") (pinfunction "B2Y_31") (pintype "bidirectional"))
      (node (ref "J1") (pin "2") (pinfunction "2_2") (pintype "passive"))
    )
    (net (code "19") (name "/GPIO_2_IN1_E16CLK") (class "Default")
      (node (ref "IC5") (pin "32") (pinfunction "B1Y_32") (pintype "bidirectional"))
      (node (ref "J1") (pin "3") (pinfunction "3_3") (pintype "passive"))
    )
    (net (code "20") (name "/GPIO_2_IN2_M16CLK") (class "Default")
      (node (ref "IC5") (pin "34") (pinfunction "A2Y_34") (pintype "bidirectional"))
      (node (ref "J1") (pin "4") (pinfunction "4_4") (pintype "passive"))
    )
    (net (code "21") (name "/GPIO_03_A3") (class "Default")
      (node (ref "IC3") (pin "27") (pinfunction "C1Y_27") (pintype "bidirectional"))
      (node (ref "SV1") (pin "6") (pinfunction "6_6") (pintype "passive"))
    )
    (net (code "22") (name "/GPIO_04_B3") (class "Default")
      (node (ref "OJ96") (pin "1") (pinfunction "1_1") (pintype "bidirectional"))
      (node (ref "SV1") (pin "7") (pinfunction "7_7") (pintype "passive"))
      (node (ref "VSLUE11") (pin "6") (pinfunction "1A3_6") (pintype "input"))
      (node (ref "VSLUE11") (pin "8") (pinfunction "1A4_8") (pintype "input"))
    )
    (net (code "23") (name "/GPIO_05_B4") (class "Default")
      (node (ref "OJ94") (pin "1") (pinfunction "1_1") (pintype "bidirectional"))
      (node (ref "SV1") (pin "8") (pinfunction "8_8") (pintype "passive"))
      (node (ref "VSLUE11") (pin "11") (pinfunction "2A1_11") (pintype "input"))
      (node (ref "VSLUE11") (pin "13") (pinfunction "2A2_13") (pintype "input"))
    )
    (net (code "24") (name "/GPIO_06_A4") (class "Default")
      (node (ref "OJ93") (pin "1") (pinfunction "1_1") (pintype "bidirectional"))
      (node (ref "SV1") (pin "9") (pinfunction "9_9") (pintype "passive"))
      (node (ref "VSLUE11") (pin "15") (pinfunction "2A3_15") (pintype "input"))
      (node (ref "VSLUE11") (pin "17") (pinfunction "2A4_17") (pintype "input"))
    )
    (net (code "25") (name "/GPIO_07_B5") (class "Default")
      (node (ref "OJ71") (pin "1") (pinfunction "1_1") (pintype "bidirectional"))
      (node (ref "SV1") (pin "10") (pinfunction "10_10") (pintype "passive"))
      (node (ref "VSLUE8") (pin "2") (pinfunction "1A1_2") (pintype "input"))
      (node (ref "VSLUE8") (pin "4") (pinfunction "1A2_4") (pintype "input"))
    )
    (net (code "26") (name "/GPIO_08_A5") (class "Default")
      (node (ref "OJ72") (pin "1") (pinfunction "1_1") (pintype "bidirectional"))
      (node (ref "SV1") (pin "13") (pinfunction "13_13") (pintype "passive"))
      (node (ref "VSLUE8") (pin "6") (pinfunction "1A3_6") (pintype "input"))
      (node (ref "VSLUE8") (pin "8") (pinfunction "1A4_8") (pintype "input"))
    )
    (net (code "27") (name "/GPIO_09_D5") (class "Default")
      (node (ref "OJ69") (pin "1") (pinfunction "1_1") (pintype "bidirectional"))
      (node (ref "SV1") (pin "14") (pinfunction "14_14") (pintype "passive"))
      (node (ref "VSLUE8") (pin "15") (pinfunction "2A3_15") (pintype "input"))
      (node (ref "VSLUE8") (pin "17") (pinfunction "2A4_17") (pintype "input"))
    )
    (net (code "28") (name "/GPIO_010_B6") (class "Default")
      (node (ref "IC7") (pin "27") (pinfunction "C1Y_27") (pintype "bidirectional"))
      (node (ref "SV1") (pin "15") (pinfunction "15_15") (pintype "passive"))
    )
    (net (code "29") (name "/GPIO_10_F13") (class "Default")
      (node (ref "IC6") (pin "34") (pinfunction "A2Y_34") (pintype "bidirectional"))
      (node (ref "SV2") (pin "2") (pinfunction "2_2") (pintype "passive"))
    )
    (net (code "30") (name "/GPIO_011_A6") (class "Default")
      (node (ref "IC7") (pin "26") (pinfunction "C2Y_26") (pintype "bidirectional"))
      (node (ref "SV1") (pin "16") (pinfunction "16_16") (pintype "passive"))
    )
    (net (code "31") (name "/GPIO_11_T15") (class "Default")
      (node (ref "IC1") (pin "26") (pinfunction "C2Y_26") (pintype "bidirectional"))
      (node (ref "SV2") (pin "4") (pinfunction "4_4") (pintype "passive"))
    )
    (net (code "32") (name "/GPIO_012_B7") (class "Default")
      (node (ref "IC3") (pin "32") (pinfunction "B1Y_32") (pintype "bidirectional"))
      (node (ref "SV1") (pin "17") (pinfunction "17_17") (pintype "passive"))
    )
    (net (code "33") (name "/GPIO_12_T14") (class "Default")
      (node (ref "IC5") (pin "26") (pinfunction "C2Y_26") (pintype "bidirectional"))
      (node (ref "SV2") (pin "5") (pinfunction "5_5") (pintype "passive"))
    )
    (net (code "34") (name "/GPIO_013_D6") (class "Default")
      (node (ref "OJ55") (pin "1") (pinfunction "1_1") (pintype "bidirectional"))
      (node (ref "SV1") (pin "18") (pinfunction "18_18") (pintype "passive"))
      (node (ref "VSLUE6") (pin "2") (pinfunction "1A1_2") (pintype "input"))
      (node (ref "VSLUE6") (pin "4") (pinfunction "1A2_4") (pintype "input"))
    )
    (net (code "35") (name "/GPIO_13_T13") (class "Default")
      (node (ref "IC2") (pin "23") (pinfunction "D2Y_23") (pintype "bidirectional"))
      (node (ref "SV2") (pin "6") (pinfunction "6_6") (pintype "passive"))
    )
    (net (code "36") (name "/GPIO_014_A7") (class "Default")
      (node (ref "IC2") (pin "35") (pinfunction "A1Y_35") (pintype "bidirectional"))
      (node (ref "SV1") (pin "19") (pinfunction "19_19") (pintype "passive"))
    )
    (net (code "37") (name "/GPIO_14_R13") (class "Default")
      (node (ref "IC5") (pin "27") (pinfunction "C1Y_27") (pintype "bidirectional"))
      (node (ref "SV2") (pin "7") (pinfunction "7_7") (pintype "passive"))
    )
    (net (code "38") (name "/GPIO_015_C6") (class "Default")
      (node (ref "OJ56") (pin "1") (pinfunction "1_1") (pintype "bidirectional"))
      (node (ref "SV1") (pin "20") (pinfunction "20_20") (pintype "passive"))
      (node (ref "VSLUE6") (pin "6") (pinfunction "1A3_6") (pintype "input"))
      (node (ref "VSLUE6") (pin "8") (pinfunction "1A4_8") (pintype "input"))
    )
    (net (code "39") (name "/GPIO_15_T12") (class "Default")
      (node (ref "IC4") (pin "24") (pinfunction "D1Y_24") (pintype "bidirectional"))
      (node (ref "SV2") (pin "8") (pinfunction "8_8") (pintype "passive"))
    )
    (net (code "40") (name "/GPIO_016_C8") (class "Default")
      (node (ref "OJ53") (pin "1") (pinfunction "1_1") (pintype "bidirectional"))
      (node (ref "SV1") (pin "21") (pinfunction "21_21") (pintype "passive"))
      (node (ref "VSLUE6") (pin "15") (pinfunction "2A3_15") (pintype "input"))
      (node (ref "VSLUE6") (pin "17") (pinfunction "2A4_17") (pintype "input"))
    )
    (net (code "41") (name "/GPIO_16_R12") (class "Default")
      (node (ref "IC4") (pin "23") (pinfunction "D2Y_23") (pintype "bidirectional"))
      (node (ref "SV2") (pin "9") (pinfunction "9_9") (pintype "passive"))
    )
    (net (code "42") (name "/GPIO_017_E6") (class "Default")
      (node (ref "OJ54") (pin "1") (pinfunction "1_1") (pintype "bidirectional"))
      (node (ref "SV1") (pin "22") (pinfunction "22_22") (pintype "passive"))
      (node (ref "VSLUE6") (pin "11") (pinfunction "2A1_11") (pintype "input"))
      (node (ref "VSLUE6") (pin "13") (pinfunction "2A2_13") (pintype "input"))
    )
    (net (code "43") (name "/GPIO_17_T11") (class "Default")
      (node (ref "J3") (pin "3") (pinfunction "P$3_3") (pintype "bidirectional"))
      (node (ref "SV2") (pin "10") (pinfunction "10_10") (pintype "passive"))
    )
    (net (code "44") (name "/GPIO_018_E7") (class "Default")
      (node (ref "IC6") (pin "23") (pinfunction "D2Y_23") (pintype "bidirectional"))
      (node (ref "SV1") (pin "23") (pinfunction "23_23") (pintype "passive"))
    )
    (net (code "45") (name "/GPIO_18_T10") (class "Default")
      (node (ref "IC3") (pin "35") (pinfunction "A1Y_35") (pintype "bidirectional"))
      (node (ref "SV2") (pin "13") (pinfunction "13_13") (pintype "passive"))
    )
    (net (code "46") (name "/GPIO_019_D8") (class "Default")
      (node (ref "J4") (pin "3") (pinfunction "P$3_3") (pintype "bidirectional"))
      (node (ref "SV1") (pin "24") (pinfunction "24_24") (pintype "passive"))
    )
    (net (code "47") (name "/GPIO_19_R11") (class "Default")
      (node (ref "IC6") (pin "35") (pinfunction "A1Y_35") (pintype "bidirectional"))
      (node (ref "SV2") (pin "14") (pinfunction "14_14") (pintype "passive"))
    )
    (net (code "48") (name "/GPIO_20_A14") (class "Default")
      (node (ref "IC4") (pin "35") (pinfunction "A1Y_35") (pintype "bidirectional"))
      (node (ref "J1") (pin "5") (pinfunction "5_5") (pintype "passive"))
    )
    (net (code "49") (name "/GPIO_020_E8") (class "Default")
      (node (ref "IC1") (pin "24") (pinfunction "D1Y_24") (pintype "bidirectional"))
      (node (ref "SV1") (pin "25") (pinfunction "25_25") (pintype "passive"))
    )
    (net (code "50") (name "/GPIO_21_B16") (class "Default")
      (node (ref "J1") (pin "6") (pinfunction "6_6") (pintype "passive"))
      (node (ref "J4") (pin "4") (pinfunction "P$4_4") (pintype "bidirectional"))
    )
    (net (code "51") (name "/GPIO_021_F8") (class "Default")
      (node (ref "IC5") (pin "35") (pinfunction "A1Y_35") (pintype "bidirectional"))
      (node (ref "SV1") (pin "26") (pinfunction "26_26") (pintype "passive"))
    )
    (net (code "52") (name "/GPIO_22_C14") (class "Default")
      (node (ref "IC8") (pin "26") (pinfunction "C2Y_26") (pintype "bidirectional"))
      (node (ref "J1") (pin "7") (pinfunction "7_7") (pintype "passive"))
    )
    (net (code "53") (name "/GPIO_022_F9") (class "Default")
      (node (ref "IC7") (pin "31") (pinfunction "B2Y_31") (pintype "bidirectional"))
      (node (ref "SV1") (pin "27") (pinfunction "27_27") (pintype "passive"))
    )
    (net (code "54") (name "/GPIO_23_C16") (class "Default")
      (node (ref "IC6") (pin "24") (pinfunction "D1Y_24") (pintype "bidirectional"))
      (node (ref "J1") (pin "8") (pinfunction "8_8") (pintype "passive"))
    )
    (net (code "55") (name "/GPIO_023_E9") (class "Default")
      (node (ref "J4") (pin "2") (pinfunction "P$2_2") (pintype "bidirectional"))
      (node (ref "SV1") (pin "28") (pinfunction "28_28") (pintype "passive"))
    )
    (net (code "56") (name "/GPIO_024_C9") (class "Default")
      (node (ref "IC4") (pin "26") (pinfunction "C2Y_26") (pintype "bidirectional"))
      (node (ref "SV1") (pin "31") (pinfunction "31_31") (pintype "passive"))
    )
    (net (code "57") (name "/GPIO_24_C15") (class "Default")
      (node (ref "IC8") (pin "27") (pinfunction "C1Y_27") (pintype "bidirectional"))
      (node (ref "J1") (pin "9") (pinfunction "9_9") (pintype "passive"))
    )
    (net (code "58") (name "/GPIO_025_D9") (class "Default")
      (node (ref "IC4") (pin "27") (pinfunction "C1Y_27") (pintype "bidirectional"))
      (node (ref "SV1") (pin "32") (pinfunction "32_32") (pintype "passive"))
    )
    (net (code "59") (name "/GPIO_25_D16") (class "Default")
      (node (ref "IC8") (pin "35") (pinfunction "A1Y_35") (pintype "bidirectional"))
      (node (ref "J1") (pin "10") (pinfunction "10_10") (pintype "passive"))
    )
    (net (code "60") (name "/GPIO_26_D15") (class "Default")
      (node (ref "IC8") (pin "24") (pinfunction "D1Y_24") (pintype "bidirectional"))
      (node (ref "J1") (pin "11") (pinfunction "11_11") (pintype "passive"))
    )
    (net (code "61") (name "/GPIO_026_E11") (class "Default")
      (node (ref "IC6") (pin "27") (pinfunction "C1Y_27") (pintype "bidirectional"))
      (node (ref "SV1") (pin "33") (pinfunction "33_33") (pintype "passive"))
    )
    (net (code "62") (name "/GPIO_27_D14") (class "Default")
      (node (ref "IC8") (pin "34") (pinfunction "A2Y_34") (pintype "bidirectional"))
      (node (ref "J1") (pin "12") (pinfunction "12_12") (pintype "passive"))
    )
    (net (code "63") (name "/GPIO_027_E10") (class "Default")
      (node (ref "OJ5") (pin "1") (pinfunction "1_1") (pintype "bidirectional"))
      (node (ref "SV1") (pin "34") (pinfunction "34_34") (pintype "passive"))
      (node (ref "VSLUE") (pin "15") (pinfunction "2A3_15") (pintype "input"))
      (node (ref "VSLUE") (pin "17") (pinfunction "2A4_17") (pintype "input"))
    )
    (net (code "64") (name "/GPIO_028_C11") (class "Default")
      (node (ref "IC7") (pin "34") (pinfunction "A2Y_34") (pintype "bidirectional"))
      (node (ref "SV1") (pin "35") (pinfunction "35_35") (pintype "passive"))
    )
    (net (code "65") (name "/GPIO_28_F15") (class "Default")
      (node (ref "IC8") (pin "32") (pinfunction "B1Y_32") (pintype "bidirectional"))
      (node (ref "J1") (pin "13") (pinfunction "13_13") (pintype "passive"))
    )
    (net (code "66") (name "/GPIO_029_B11") (class "Default")
      (node (ref "OJ6") (pin "1") (pinfunction "1_1") (pintype "bidirectional"))
      (node (ref "SV1") (pin "36") (pinfunction "36_36") (pintype "passive"))
      (node (ref "VSLUE") (pin "11") (pinfunction "2A1_11") (pintype "input"))
      (node (ref "VSLUE") (pin "13") (pinfunction "2A2_13") (pintype "input"))
    )
    (net (code "67") (name "/GPIO_29_F16") (class "Default")
      (node (ref "IC8") (pin "31") (pinfunction "B2Y_31") (pintype "bidirectional"))
      (node (ref "J1") (pin "14") (pinfunction "14_14") (pintype "passive"))
    )
    (net (code "68") (name "/GPIO_030_A12") (class "Default")
      (node (ref "IC2") (pin "26") (pinfunction "C2Y_26") (pintype "bidirectional"))
      (node (ref "SV1") (pin "37") (pinfunction "37_37") (pintype "passive"))
    )
    (net (code "69") (name "/GPIO_031_D11") (class "Default")
      (node (ref "OJ8") (pin "1") (pinfunction "1_1") (pintype "bidirectional"))
      (node (ref "SV1") (pin "38") (pinfunction "38_38") (pintype "passive"))
      (node (ref "VSLUE") (pin "6") (pinfunction "1A3_6") (pintype "input"))
      (node (ref "VSLUE") (pin "8") (pinfunction "1A4_8") (pintype "input"))
    )
    (net (code "70") (name "/GPIO_032_D12") (class "Default")
      (node (ref "OJ95") (pin "1") (pinfunction "1_1") (pintype "bidirectional"))
      (node (ref "SV1") (pin "39") (pinfunction "39_39") (pintype "passive"))
      (node (ref "VSLUE11") (pin "2") (pinfunction "1A1_2") (pintype "input"))
      (node (ref "VSLUE11") (pin "4") (pinfunction "1A2_4") (pintype "input"))
    )
    (net (code "71") (name "/GPIO_033_B12") (class "Default")
      (node (ref "IC2") (pin "24") (pinfunction "D1Y_24") (pintype "bidirectional"))
      (node (ref "SV1") (pin "40") (pinfunction "40_40") (pintype "passive"))
    )
    (net (code "72") (name "/GPIO_110_P11") (class "Default")
      (node (ref "IC6") (pin "26") (pinfunction "C2Y_26") (pintype "bidirectional"))
      (node (ref "SV2") (pin "15") (pinfunction "15_15") (pintype "passive"))
    )
    (net (code "73") (name "/GPIO_111_R10") (class "Default")
      (node (ref "IC3") (pin "34") (pinfunction "A2Y_34") (pintype "bidirectional"))
      (node (ref "SV2") (pin "16") (pinfunction "16_16") (pintype "passive"))
    )
    (net (code "74") (name "/GPIO_112_N12") (class "Default")
      (node (ref "J4") (pin "1") (pinfunction "P$1_1") (pintype "bidirectional"))
      (node (ref "SV2") (pin "17") (pinfunction "17_17") (pintype "passive"))
    )
    (net (code "75") (name "/GPIO_113_P9") (class "Default")
      (node (ref "IC7") (pin "24") (pinfunction "D1Y_24") (pintype "bidirectional"))
      (node (ref "SV2") (pin "18") (pinfunction "18_18") (pintype "passive"))
    )
    (net (code "76") (name "/GPIO_114_N9") (class "Default")
      (node (ref "J3") (pin "4") (pinfunction "P$4_4") (pintype "bidirectional"))
      (node (ref "LED1") (pin "A") (pinfunction "A_A") (pintype "passive"))
      (node (ref "R17") (pin "P$2") (pinfunction "2_P$2") (pintype "passive"))
      (node (ref "SV2") (pin "19") (pinfunction "19_19") (pintype "passive"))
      (node (ref "VSLUE") (pin "1") (pinfunction "~{1OE}_1") (pintype "input"))
      (node (ref "VSLUE") (pin "19") (pinfunction "~{2OE}_19") (pintype "input"))
      (node (ref "VSLUE11") (pin "1") (pinfunction "~{1OE}_1") (pintype "input"))
      (node (ref "VSLUE11") (pin "19") (pinfunction "~{2OE}_19") (pintype "input"))
      (node (ref "VSLUE6") (pin "1") (pinfunction "~{1OE}_1") (pintype "input"))
      (node (ref "VSLUE6") (pin "19") (pinfunction "~{2OE}_19") (pintype "input"))
      (node (ref "VSLUE8") (pin "1") (pinfunction "~{1OE}_1") (pintype "input"))
      (node (ref "VSLUE8") (pin "19") (pinfunction "~{2OE}_19") (pintype "input"))
    )
    (net (code "77") (name "/GPIO_115_N11") (class "Default")
      (node (ref "IC7") (pin "23") (pinfunction "D2Y_23") (pintype "bidirectional"))
      (node (ref "SV2") (pin "20") (pinfunction "20_20") (pintype "passive"))
    )
    (net (code "78") (name "/GPIO_116_L16") (class "Default")
      (node (ref "IC2") (pin "34") (pinfunction "A2Y_34") (pintype "bidirectional"))
      (node (ref "SV2") (pin "21") (pinfunction "21_21") (pintype "passive"))
    )
    (net (code "79") (name "/GPIO_117_K16") (class "Default")
      (node (ref "IC2") (pin "32") (pinfunction "B1Y_32") (pintype "bidirectional"))
      (node (ref "SV2") (pin "22") (pinfunction "22_22") (pintype "passive"))
    )
    (net (code "80") (name "/GPIO_118_R16") (class "Default")
      (node (ref "IC2") (pin "31") (pinfunction "B2Y_31") (pintype "bidirectional"))
      (node (ref "SV2") (pin "23") (pinfunction "23_23") (pintype "passive"))
    )
    (net (code "81") (name "/GPIO_119_L15") (class "Default")
      (node (ref "IC1") (pin "27") (pinfunction "C1Y_27") (pintype "bidirectional"))
      (node (ref "SV2") (pin "24") (pinfunction "24_24") (pintype "passive"))
    )
    (net (code "82") (name "/GPIO_120_P15") (class "Default")
      (node (ref "IC7") (pin "32") (pinfunction "B1Y_32") (pintype "bidirectional"))
      (node (ref "SV2") (pin "25") (pinfunction "25_25") (pintype "passive"))
    )
    (net (code "83") (name "/GPIO_121_P16") (class "Default")
      (node (ref "IC1") (pin "23") (pinfunction "D2Y_23") (pintype "bidirectional"))
      (node (ref "SV2") (pin "26") (pinfunction "26_26") (pintype "passive"))
    )
    (net (code "84") (name "/GPIO_122_R14") (class "Default")
      (node (ref "IC1") (pin "32") (pinfunction "B1Y_32") (pintype "bidirectional"))
      (node (ref "SV2") (pin "27") (pinfunction "27_27") (pintype "passive"))
    )
    (net (code "85") (name "/GPIO_123_N16") (class "Default")
      (node (ref "IC1") (pin "35") (pinfunction "A1Y_35") (pintype "bidirectional"))
      (node (ref "SV2") (pin "28") (pinfunction "28_28") (pintype "passive"))
    )
    (net (code "86") (name "/GPIO_124_N15") (class "Default")
      (node (ref "IC1") (pin "31") (pinfunction "B2Y_31") (pintype "bidirectional"))
      (node (ref "SV2") (pin "31") (pinfunction "31_31") (pintype "passive"))
    )
    (net (code "87") (name "/GPIO_125_P14") (class "Default")
      (node (ref "IC1") (pin "34") (pinfunction "A2Y_34") (pintype "bidirectional"))
      (node (ref "SV2") (pin "32") (pinfunction "32_32") (pintype "passive"))
    )
    (net (code "88") (name "/GPIO_126_L14") (class "Default")
      (node (ref "IC6") (pin "31") (pinfunction "B2Y_31") (pintype "bidirectional"))
      (node (ref "SV2") (pin "33") (pinfunction "33_33") (pintype "passive"))
    )
    (net (code "89") (name "/GPIO_127_N14") (class "Default")
      (node (ref "OJ70") (pin "1") (pinfunction "1_1") (pintype "bidirectional"))
      (node (ref "SV2") (pin "34") (pinfunction "34_34") (pintype "passive"))
      (node (ref "VSLUE8") (pin "11") (pinfunction "2A1_11") (pintype "input"))
      (node (ref "VSLUE8") (pin "13") (pinfunction "2A2_13") (pintype "input"))
    )
    (net (code "90") (name "/GPIO_128_M10") (class "Default")
      (node (ref "J12") (pin "2") (pinfunction "P$2_2") (pintype "bidirectional"))
      (node (ref "SV2") (pin "35") (pinfunction "35_35") (pintype "passive"))
    )
    (net (code "91") (name "/GPIO_129_L13") (class "Default")
      (node (ref "IC6") (pin "32") (pinfunction "B1Y_32") (pintype "bidirectional"))
      (node (ref "SV2") (pin "36") (pinfunction "36_36") (pintype "passive"))
    )
    (net (code "92") (name "/GPIO_130_J16") (class "Default")
      (node (ref "J12") (pin "1") (pinfunction "P$1_1") (pintype "bidirectional"))
      (node (ref "SV2") (pin "37") (pinfunction "37_37") (pintype "passive"))
    )
    (net (code "93") (name "/GPIO_131_K15") (class "Default")
      (node (ref "IC2") (pin "27") (pinfunction "C1Y_27") (pintype "bidirectional"))
      (node (ref "SV2") (pin "38") (pinfunction "38_38") (pintype "passive"))
    )
    (net (code "94") (name "/GPIO_132_J13") (class "Default")
      (node (ref "IC7") (pin "35") (pinfunction "A1Y_35") (pintype "bidirectional"))
      (node (ref "SV2") (pin "39") (pinfunction "39_39") (pintype "passive"))
    )
    (net (code "95") (name "/GPIO_133_J14") (class "Default")
      (node (ref "OJ7") (pin "1") (pinfunction "1_1") (pintype "bidirectional"))
      (node (ref "SV2") (pin "40") (pinfunction "40_40") (pintype "passive"))
      (node (ref "VSLUE") (pin "2") (pinfunction "1A1_2") (pintype "input"))
      (node (ref "VSLUE") (pin "4") (pinfunction "1A2_4") (pintype "input"))
    )
    (net (code "96") (name "/GPIO_210_F14") (class "Default")
      (node (ref "IC8") (pin "23") (pinfunction "D2Y_23") (pintype "bidirectional"))
      (node (ref "J1") (pin "15") (pinfunction "15_15") (pintype "passive"))
    )
    (net (code "97") (name "/GPIO_211_G16") (class "Default")
      (node (ref "IC4") (pin "34") (pinfunction "A2Y_34") (pintype "bidirectional"))
      (node (ref "J1") (pin "16") (pinfunction "16_16") (pintype "passive"))
    )
    (net (code "98") (name "/GPIO_212_G15") (class "Default")
      (node (ref "IC4") (pin "32") (pinfunction "B1Y_32") (pintype "bidirectional"))
      (node (ref "J1") (pin "17") (pinfunction "17_17") (pintype "passive"))
    )
    (net (code "99") (name "GND") (class "Default")
      (node (ref "A4") (pin "2") (pinfunction "2_2") (pintype "passive"))
      (node (ref "A4") (pin "3") (pinfunction "2_3") (pintype "passive"))
      (node (ref "A4") (pin "4") (pinfunction "2_4") (pintype "passive"))
      (node (ref "A4") (pin "5") (pinfunction "2_5") (pintype "passive"))
      (node (ref "A5") (pin "2") (pinfunction "2_2") (pintype "passive"))
      (node (ref "A5") (pin "3") (pinfunction "2_3") (pintype "passive"))
      (node (ref "A5") (pin "4") (pinfunction "2_4") (pintype "passive"))
      (node (ref "A5") (pin "5") (pinfunction "2_5") (pintype "passive"))
      (node (ref "B11") (pin "2") (pinfunction "2_2") (pintype "passive"))
      (node (ref "B11") (pin "3") (pinfunction "2_3") (pintype "passive"))
      (node (ref "B11") (pin "4") (pinfunction "2_4") (pintype "passive"))
      (node (ref "B11") (pin "5") (pinfunction "2_5") (pintype "passive"))
      (node (ref "B3") (pin "2") (pinfunction "2_2") (pintype "passive"))
      (node (ref "B3") (pin "3") (pinfunction "2_3") (pintype "passive"))
      (node (ref "B3") (pin "4") (pinfunction "2_4") (pintype "passive"))
      (node (ref "B3") (pin "5") (pinfunction "2_5") (pintype "passive"))
      (node (ref "B4") (pin "2") (pinfunction "2_2") (pintype "passive"))
      (node (ref "B4") (pin "3") (pinfunction "2_3") (pintype "passive"))
      (node (ref "B4") (pin "4") (pinfunction "2_4") (pintype "passive"))
      (node (ref "B4") (pin "5") (pinfunction "2_5") (pintype "passive"))
      (node (ref "B5") (pin "2") (pinfunction "2_2") (pintype "passive"))
      (node (ref "B5") (pin "3") (pinfunction "2_3") (pintype "passive"))
      (node (ref "B5") (pin "4") (pinfunction "2_4") (pintype "passive"))
      (node (ref "B5") (pin "5") (pinfunction "2_5") (pintype "passive"))
      (node (ref "C1") (pin "1") (pinfunction "1_1") (pintype "passive"))
      (node (ref "C10") (pin "1") (pinfunction "1_1") (pintype "passive"))
      (node (ref "C11") (pin "1") (pinfunction "1_1") (pintype "passive"))
      (node (ref "C12") (pin "1") (pinfunction "1_1") (pintype "passive"))
      (node (ref "C2") (pin "1") (pinfunction "1_1") (pintype "passive"))
      (node (ref "C3") (pin "1") (pinfunction "1_1") (pintype "passive"))
      (node (ref "C4") (pin "1") (pinfunction "1_1") (pintype "passive"))
      (node (ref "C5") (pin "1") (pinfunction "1_1") (pintype "passive"))
      (node (ref "C6") (pin "2") (pinfunction "2_2") (pintype "passive"))
      (node (ref "C6") (pin "3") (pinfunction "2_3") (pintype "passive"))
      (node (ref "C6") (pin "4") (pinfunction "2_4") (pintype "passive"))
      (node (ref "C6") (pin "5") (pinfunction "2_5") (pintype "passive"))
      (node (ref "C7") (pin "1") (pinfunction "1_1") (pintype "passive"))
      (node (ref "C8") (pin "2") (pinfunction "2_2") (pintype "passive"))
      (node (ref "C8") (pin "3") (pinfunction "2_3") (pintype "passive"))
      (node (ref "C8") (pin "4") (pinfunction "2_4") (pintype "passive"))
      (node (ref "C8") (pin "5") (pinfunction "2_5") (pintype "passive"))
      (node (ref "C9") (pin "1") (pinfunction "1_1") (pintype "passive"))
      (node (ref "C91") (pin "1") (pinfunction "1_1") (pintype "passive"))
      (node (ref "C97") (pin "1") (pinfunction "1_1") (pintype "passive"))
      (node (ref "CP1") (pin "2") (pinfunction "2_2") (pintype "passive"))
      (node (ref "CP11") (pin "1") (pinfunction "1_1") (pintype "passive"))
      (node (ref "CP2") (pin "2") (pinfunction "2_2") (pintype "passive"))
      (node (ref "CP3") (pin "2") (pinfunction "2_2") (pintype "passive"))
      (node (ref "CP4") (pin "1") (pinfunction "1_1") (pintype "passive"))
      (node (ref "CP6") (pin "2") (pinfunction "2_2") (pintype "passive"))
      (node (ref "D11") (pin "2") (pinfunction "2_2") (pintype "passive"))
      (node (ref "D11") (pin "3") (pinfunction "2_3") (pintype "passive"))
      (node (ref "D11") (pin "4") (pinfunction "2_4") (pintype "passive"))
      (node (ref "D11") (pin "5") (pinfunction "2_5") (pintype "passive"))
      (node (ref "D12") (pin "2") (pinfunction "2_2") (pintype "passive"))
      (node (ref "D12") (pin "3") (pinfunction "2_3") (pintype "passive"))
      (node (ref "D12") (pin "4") (pinfunction "2_4") (pintype "passive"))
      (node (ref "D12") (pin "5") (pinfunction "2_5") (pintype "passive"))
      (node (ref "D5") (pin "2") (pinfunction "2_2") (pintype "passive"))
      (node (ref "D5") (pin "3") (pinfunction "2_3") (pintype "passive"))
      (node (ref "D5") (pin "4") (pinfunction "2_4") (pintype "passive"))
      (node (ref "D5") (pin "5") (pinfunction "2_5") (pintype "passive"))
      (node (ref "D6") (pin "2") (pinfunction "2_2") (pintype "passive"))
      (node (ref "D6") (pin "3") (pinfunction "2_3") (pintype "passive"))
      (node (ref "D6") (pin "4") (pinfunction "2_4") (pintype "passive"))
      (node (ref "D6") (pin "5") (pinfunction "2_5") (pintype "passive"))
      (node (ref "E10") (pin "2") (pinfunction "2_2") (pintype "passive"))
      (node (ref "E10") (pin "3") (pinfunction "2_3") (pintype "passive"))
      (node (ref "E10") (pin "4") (pinfunction "2_4") (pintype "passive"))
      (node (ref "E10") (pin "5") (pinfunction "2_5") (pintype "passive"))
      (node (ref "E6") (pin "2") (pinfunction "2_2") (pintype "passive"))
      (node (ref "E6") (pin "3") (pinfunction "2_3") (pintype "passive"))
      (node (ref "E6") (pin "4") (pinfunction "2_4") (pintype "passive"))
      (node (ref "E6") (pin "5") (pinfunction "2_5") (pintype "passive"))
      (node (ref "IC1") (pin "10") (pinfunction "AGND_2_10") (pintype "bidirectional"))
      (node (ref "IC1") (pin "15") (pinfunction "AGND_3_15") (pintype "bidirectional"))
      (node (ref "IC1") (pin "20") (pinfunction "GND_1_20") (pintype "bidirectional"))
      (node (ref "IC1") (pin "28") (pinfunction "DGND_1_28") (pintype "bidirectional"))
      (node (ref "IC1") (pin "30") (pinfunction "DGND_2_30") (pintype "bidirectional"))
      (node (ref "IC1") (pin "38") (pinfunction "GND_2_38") (pintype "bidirectional"))
      (node (ref "IC1") (pin "5") (pinfunction "AGND_1_5") (pintype "bidirectional"))
      (node (ref "IC2") (pin "10") (pinfunction "AGND_2_10") (pintype "bidirectional"))
      (node (ref "IC2") (pin "15") (pinfunction "AGND_3_15") (pintype "bidirectional"))
      (node (ref "IC2") (pin "20") (pinfunction "GND_1_20") (pintype "bidirectional"))
      (node (ref "IC2") (pin "28") (pinfunction "DGND_1_28") (pintype "bidirectional"))
      (node (ref "IC2") (pin "30") (pinfunction "DGND_2_30") (pintype "bidirectional"))
      (node (ref "IC2") (pin "38") (pinfunction "GND_2_38") (pintype "bidirectional"))
      (node (ref "IC2") (pin "5") (pinfunction "AGND_1_5") (pintype "bidirectional"))
      (node (ref "IC3") (pin "10") (pinfunction "AGND_2_10") (pintype "bidirectional"))
      (node (ref "IC3") (pin "15") (pinfunction "AGND_3_15") (pintype "bidirectional"))
      (node (ref "IC3") (pin "20") (pinfunction "GND_1_20") (pintype "bidirectional"))
      (node (ref "IC3") (pin "28") (pinfunction "DGND_1_28") (pintype "bidirectional"))
      (node (ref "IC3") (pin "30") (pinfunction "DGND_2_30") (pintype "bidirectional"))
      (node (ref "IC3") (pin "38") (pinfunction "GND_2_38") (pintype "bidirectional"))
      (node (ref "IC3") (pin "5") (pinfunction "AGND_1_5") (pintype "bidirectional"))
      (node (ref "IC4") (pin "10") (pinfunction "AGND_2_10") (pintype "bidirectional"))
      (node (ref "IC4") (pin "15") (pinfunction "AGND_3_15") (pintype "bidirectional"))
      (node (ref "IC4") (pin "20") (pinfunction "GND_1_20") (pintype "bidirectional"))
      (node (ref "IC4") (pin "28") (pinfunction "DGND_1_28") (pintype "bidirectional"))
      (node (ref "IC4") (pin "30") (pinfunction "DGND_2_30") (pintype "bidirectional"))
      (node (ref "IC4") (pin "38") (pinfunction "GND_2_38") (pintype "bidirectional"))
      (node (ref "IC4") (pin "5") (pinfunction "AGND_1_5") (pintype "bidirectional"))
      (node (ref "IC5") (pin "10") (pinfunction "AGND_2_10") (pintype "bidirectional"))
      (node (ref "IC5") (pin "15") (pinfunction "AGND_3_15") (pintype "bidirectional"))
      (node (ref "IC5") (pin "20") (pinfunction "GND_1_20") (pintype "bidirectional"))
      (node (ref "IC5") (pin "28") (pinfunction "DGND_1_28") (pintype "bidirectional"))
      (node (ref "IC5") (pin "30") (pinfunction "DGND_2_30") (pintype "bidirectional"))
      (node (ref "IC5") (pin "38") (pinfunction "GND_2_38") (pintype "bidirectional"))
      (node (ref "IC5") (pin "5") (pinfunction "AGND_1_5") (pintype "bidirectional"))
      (node (ref "IC6") (pin "10") (pinfunction "AGND_2_10") (pintype "bidirectional"))
      (node (ref "IC6") (pin "15") (pinfunction "AGND_3_15") (pintype "bidirectional"))
      (node (ref "IC6") (pin "20") (pinfunction "GND_1_20") (pintype "bidirectional"))
      (node (ref "IC6") (pin "28") (pinfunction "DGND_1_28") (pintype "bidirectional"))
      (node (ref "IC6") (pin "30") (pinfunction "DGND_2_30") (pintype "bidirectional"))
      (node (ref "IC6") (pin "38") (pinfunction "GND_2_38") (pintype "bidirectional"))
      (node (ref "IC6") (pin "5") (pinfunction "AGND_1_5") (pintype "bidirectional"))
      (node (ref "IC7") (pin "10") (pinfunction "AGND_2_10") (pintype "bidirectional"))
      (node (ref "IC7") (pin "15") (pinfunction "AGND_3_15") (pintype "bidirectional"))
      (node (ref "IC7") (pin "20") (pinfunction "GND_1_20") (pintype "bidirectional"))
      (node (ref "IC7") (pin "28") (pinfunction "DGND_1_28") (pintype "bidirectional"))
      (node (ref "IC7") (pin "30") (pinfunction "DGND_2_30") (pintype "bidirectional"))
      (node (ref "IC7") (pin "38") (pinfunction "GND_2_38") (pintype "bidirectional"))
      (node (ref "IC7") (pin "5") (pinfunction "AGND_1_5") (pintype "bidirectional"))
      (node (ref "IC8") (pin "10") (pinfunction "AGND_2_10") (pintype "bidirectional"))
      (node (ref "IC8") (pin "15") (pinfunction "AGND_3_15") (pintype "bidirectional"))
      (node (ref "IC8") (pin "20") (pinfunction "GND_1_20") (pintype "bidirectional"))
      (node (ref "IC8") (pin "28") (pinfunction "DGND_1_28") (pintype "bidirectional"))
      (node (ref "IC8") (pin "30") (pinfunction "DGND_2_30") (pintype "bidirectional"))
      (node (ref "IC8") (pin "38") (pinfunction "GND_2_38") (pintype "bidirectional"))
      (node (ref "IC8") (pin "5") (pinfunction "AGND_1_5") (pintype "bidirectional"))
      (node (ref "J1") (pin "26") (pinfunction "26_26") (pintype "passive"))
      (node (ref "J12") (pin "3") (pinfunction "P$3_3") (pintype "bidirectional"))
      (node (ref "J14") (pin "2") (pinfunction "2_2") (pintype "passive"))
      (node (ref "J14") (pin "3") (pinfunction "2_3") (pintype "passive"))
      (node (ref "J14") (pin "4") (pinfunction "2_4") (pintype "passive"))
      (node (ref "J14") (pin "5") (pinfunction "2_5") (pintype "passive"))
      (node (ref "J19") (pin "1-A9") (pinfunction "MS_1-A9") (pintype "passive"))
      (node (ref "J19") (pin "1-C9") (pinfunction "MS_1-C9") (pintype "passive"))
      (node (ref "J19") (pin "2-A9") (pinfunction "MS_2-A9") (pintype "passive"))
      (node (ref "J19") (pin "2-C9") (pinfunction "MS_2-C9") (pintype "passive"))
      (node (ref "J3") (pin "1") (pinfunction "P$1_1") (pintype "bidirectional"))
      (node (ref "N14") (pin "2") (pinfunction "2_2") (pintype "passive"))
      (node (ref "N14") (pin "3") (pinfunction "2_3") (pintype "passive"))
      (node (ref "N14") (pin "4") (pinfunction "2_4") (pintype "passive"))
      (node (ref "N14") (pin "5") (pinfunction "2_5") (pintype "passive"))
      (node (ref "OJ1") (pin "2") (pinfunction "2_2") (pintype "bidirectional"))
      (node (ref "OJ2") (pin "2") (pinfunction "2_2") (pintype "bidirectional"))
      (node (ref "OJ3") (pin "2") (pinfunction "2_2") (pintype "bidirectional"))
      (node (ref "OJ4") (pin "2") (pinfunction "2_2") (pintype "bidirectional"))
      (node (ref "OJ49") (pin "2") (pinfunction "2_2") (pintype "bidirectional"))
      (node (ref "OJ5") (pin "2") (pinfunction "2_2") (pintype "bidirectional"))
      (node (ref "OJ50") (pin "2") (pinfunction "2_2") (pintype "bidirectional"))
      (node (ref "OJ51") (pin "2") (pinfunction "2_2") (pintype "bidirectional"))
      (node (ref "OJ52") (pin "2") (pinfunction "2_2") (pintype "bidirectional"))
      (node (ref "OJ53") (pin "2") (pinfunction "2_2") (pintype "bidirectional"))
      (node (ref "OJ54") (pin "2") (pinfunction "2_2") (pintype "bidirectional"))
      (node (ref "OJ55") (pin "2") (pinfunction "2_2") (pintype "bidirectional"))
      (node (ref "OJ56") (pin "2") (pinfunction "2_2") (pintype "bidirectional"))
      (node (ref "OJ6") (pin "2") (pinfunction "2_2") (pintype "bidirectional"))
      (node (ref "OJ65") (pin "2") (pinfunction "2_2") (pintype "bidirectional"))
      (node (ref "OJ66") (pin "2") (pinfunction "2_2") (pintype "bidirectional"))
      (node (ref "OJ67") (pin "2") (pinfunction "2_2") (pintype "bidirectional"))
      (node (ref "OJ68") (pin "2") (pinfunction "2_2") (pintype "bidirectional"))
      (node (ref "OJ69") (pin "2") (pinfunction "2_2") (pintype "bidirectional"))
      (node (ref "OJ7") (pin "2") (pinfunction "2_2") (pintype "bidirectional"))
      (node (ref "OJ70") (pin "2") (pinfunction "2_2") (pintype "bidirectional"))
      (node (ref "OJ71") (pin "2") (pinfunction "2_2") (pintype "bidirectional"))
      (node (ref "OJ72") (pin "2") (pinfunction "2_2") (pintype "bidirectional"))
      (node (ref "OJ8") (pin "2") (pinfunction "2_2") (pintype "bidirectional"))
      (node (ref "OJ89") (pin "2") (pinfunction "2_2") (pintype "bidirectional"))
      (node (ref "OJ90") (pin "2") (pinfunction "2_2") (pintype "bidirectional"))
      (node (ref "OJ91") (pin "2") (pinfunction "2_2") (pintype "bidirectional"))
      (node (ref "OJ92") (pin "2") (pinfunction "2_2") (pintype "bidirectional"))
      (node (ref "OJ93") (pin "2") (pinfunction "2_2") (pintype "bidirectional"))
      (node (ref "OJ94") (pin "2") (pinfunction "2_2") (pintype "bidirectional"))
      (node (ref "OJ95") (pin "2") (pinfunction "2_2") (pintype "bidirectional"))
      (node (ref "OJ96") (pin "2") (pinfunction "2_2") (pintype "bidirectional"))
      (node (ref "R8") (pin "2") (pinfunction "2_2") (pintype "passive"))
      (node (ref "REG") (pin "1") (pinfunction "GND_1") (pintype "bidirectional"))
      (node (ref "REG1") (pin "1") (pinfunction "GND_1") (pintype "bidirectional"))
      (node (ref "RLEDPOW") (pin "2") (pinfunction "2_2") (pintype "passive"))
      (node (ref "RLEDPOW1") (pin "2") (pinfunction "2_2") (pintype "passive"))
      (node (ref "SV1") (pin "12") (pinfunction "12_12") (pintype "passive"))
      (node (ref "SV1") (pin "30") (pinfunction "30_30") (pintype "passive"))
      (node (ref "SV2") (pin "12") (pinfunction "12_12") (pintype "passive"))
      (node (ref "SV2") (pin "30") (pinfunction "30_30") (pintype "passive"))
      (node (ref "VSLUE") (pin "10") (pinfunction "GND_10") (pintype "power_in"))
      (node (ref "VSLUE11") (pin "10") (pinfunction "GND_10") (pintype "power_in"))
      (node (ref "VSLUE6") (pin "10") (pinfunction "GND_10") (pintype "power_in"))
      (node (ref "VSLUE8") (pin "10") (pinfunction "GND_10") (pintype "power_in"))
    )
    (net (code "100") (name "Net-(IC1-A1A)") (class "Default")
      (node (ref "IC1") (pin "1") (pinfunction "A1A_1") (pintype "bidirectional"))
      (node (ref "J5") (pin "8") (pinfunction "8_8") (pintype "bidirectional"))
    )
    (net (code "101") (name "Net-(IC1-A1B)") (class "Default")
      (node (ref "IC1") (pin "2") (pinfunction "A1B_2") (pintype "bidirectional"))
      (node (ref "J5") (pin "7") (pinfunction "7_7") (pintype "bidirectional"))
    )
    (net (code "102") (name "Net-(IC1-A2A)") (class "Default")
      (node (ref "IC1") (pin "3") (pinfunction "A2A_3") (pintype "bidirectional"))
      (node (ref "J5") (pin "6") (pinfunction "6_6") (pintype "bidirectional"))
    )
    (net (code "103") (name "Net-(IC1-A2B)") (class "Default")
      (node (ref "IC1") (pin "4") (pinfunction "A2B_4") (pintype "bidirectional"))
      (node (ref "J5") (pin "3") (pinfunction "3_3") (pintype "bidirectional"))
    )
    (net (code "104") (name "Net-(IC1-B1A)") (class "Default")
      (node (ref "IC1") (pin "6") (pinfunction "B1A_6") (pintype "bidirectional"))
      (node (ref "J5") (pin "5") (pinfunction "5_5") (pintype "bidirectional"))
    )
    (net (code "105") (name "Net-(IC1-B1B)") (class "Default")
      (node (ref "IC1") (pin "7") (pinfunction "B1B_7") (pintype "bidirectional"))
      (node (ref "J5") (pin "4") (pinfunction "4_4") (pintype "bidirectional"))
    )
    (net (code "106") (name "Net-(IC1-B2A)") (class "Default")
      (node (ref "IC1") (pin "8") (pinfunction "B2A_8") (pintype "bidirectional"))
      (node (ref "J5") (pin "2") (pinfunction "2_2") (pintype "bidirectional"))
    )
    (net (code "107") (name "Net-(IC1-B2B)") (class "Default")
      (node (ref "IC1") (pin "9") (pinfunction "B2B_9") (pintype "bidirectional"))
      (node (ref "J5") (pin "1") (pinfunction "1_1") (pintype "bidirectional"))
    )
    (net (code "108") (name "Net-(IC1-C1A)") (class "Default")
      (node (ref "IC1") (pin "11") (pinfunction "C1A_11") (pintype "bidirectional"))
      (node (ref "J6") (pin "8") (pinfunction "8_8") (pintype "bidirectional"))
    )
    (net (code "109") (name "Net-(IC1-C1B)") (class "Default")
      (node (ref "IC1") (pin "12") (pinfunction "C1B_12") (pintype "bidirectional"))
      (node (ref "J6") (pin "7") (pinfunction "7_7") (pintype "bidirectional"))
    )
    (net (code "110") (name "Net-(IC1-C2A)") (class "Default")
      (node (ref "IC1") (pin "13") (pinfunction "C2A_13") (pintype "bidirectional"))
      (node (ref "J6") (pin "6") (pinfunction "6_6") (pintype "bidirectional"))
    )
    (net (code "111") (name "Net-(IC1-C2B)") (class "Default")
      (node (ref "IC1") (pin "14") (pinfunction "C2B_14") (pintype "bidirectional"))
      (node (ref "J6") (pin "3") (pinfunction "3_3") (pintype "bidirectional"))
    )
    (net (code "112") (name "Net-(IC1-D1A)") (class "Default")
      (node (ref "IC1") (pin "16") (pinfunction "D1A_16") (pintype "bidirectional"))
      (node (ref "J6") (pin "5") (pinfunction "5_5") (pintype "bidirectional"))
    )
    (net (code "113") (name "Net-(IC1-D1B)") (class "Default")
      (node (ref "IC1") (pin "17") (pinfunction "D1B_17") (pintype "bidirectional"))
      (node (ref "J6") (pin "4") (pinfunction "4_4") (pintype "bidirectional"))
    )
    (net (code "114") (name "Net-(IC1-D2A)") (class "Default")
      (node (ref "IC1") (pin "18") (pinfunction "D2A_18") (pintype "bidirectional"))
      (node (ref "J6") (pin "2") (pinfunction "2_2") (pintype "bidirectional"))
    )
    (net (code "115") (name "Net-(IC1-D2B)") (class "Default")
      (node (ref "IC1") (pin "19") (pinfunction "D2B_19") (pintype "bidirectional"))
      (node (ref "J6") (pin "1") (pinfunction "1_1") (pintype "bidirectional"))
    )
    (net (code "116") (name "Net-(IC2-A1A)") (class "Default")
      (node (ref "IC2") (pin "1") (pinfunction "A1A_1") (pintype "bidirectional"))
      (node (ref "JP2") (pin "1") (pinfunction "1_1") (pintype "passive"))
    )
    (net (code "117") (name "Net-(IC2-A1B)") (class "Default")
      (node (ref "IC2") (pin "2") (pinfunction "A1B_2") (pintype "bidirectional"))
      (node (ref "JP2") (pin "2") (pinfunction "2_2") (pintype "passive"))
    )
    (net (code "118") (name "Net-(IC2-A2A)") (class "Default")
      (node (ref "IC2") (pin "3") (pinfunction "A2A_3") (pintype "bidirectional"))
      (node (ref "JP2") (pin "3") (pinfunction "3_3") (pintype "passive"))
    )
    (net (code "119") (name "Net-(IC2-A2B)") (class "Default")
      (node (ref "IC2") (pin "4") (pinfunction "A2B_4") (pintype "bidirectional"))
      (node (ref "JP2") (pin "4") (pinfunction "4_4") (pintype "passive"))
    )
    (net (code "120") (name "Net-(IC2-B1A)") (class "Default")
      (node (ref "IC2") (pin "6") (pinfunction "B1A_6") (pintype "bidirectional"))
      (node (ref "JP2") (pin "5") (pinfunction "5_5") (pintype "passive"))
    )
    (net (code "121") (name "Net-(IC2-B1B)") (class "Default")
      (node (ref "IC2") (pin "7") (pinfunction "B1B_7") (pintype "bidirectional"))
      (node (ref "JP2") (pin "6") (pinfunction "6_6") (pintype "passive"))
    )
    (net (code "122") (name "Net-(IC2-B2A)") (class "Default")
      (node (ref "IC2") (pin "8") (pinfunction "B2A_8") (pintype "bidirectional"))
      (node (ref "JP2") (pin "7") (pinfunction "7_7") (pintype "passive"))
    )
    (net (code "123") (name "Net-(IC2-B2B)") (class "Default")
      (node (ref "IC2") (pin "9") (pinfunction "B2B_9") (pintype "bidirectional"))
      (node (ref "JP2") (pin "8") (pinfunction "8_8") (pintype "passive"))
    )
    (net (code "124") (name "Net-(IC2-C1A)") (class "Default")
      (node (ref "IC2") (pin "11") (pinfunction "C1A_11") (pintype "bidirectional"))
      (node (ref "JP2") (pin "9") (pinfunction "9_9") (pintype "passive"))
    )
    (net (code "125") (name "Net-(IC2-C1B)") (class "Default")
      (node (ref "IC2") (pin "12") (pinfunction "C1B_12") (pintype "bidirectional"))
      (node (ref "JP2") (pin "10") (pinfunction "10_10") (pintype "passive"))
    )
    (net (code "126") (name "Net-(IC2-C2A)") (class "Default")
      (node (ref "IC2") (pin "13") (pinfunction "C2A_13") (pintype "bidirectional"))
      (node (ref "JP2") (pin "11") (pinfunction "11_11") (pintype "passive"))
    )
    (net (code "127") (name "Net-(IC2-C2B)") (class "Default")
      (node (ref "IC2") (pin "14") (pinfunction "C2B_14") (pintype "bidirectional"))
      (node (ref "JP2") (pin "12") (pinfunction "12_12") (pintype "passive"))
    )
    (net (code "128") (name "Net-(IC2-D1A)") (class "Default")
      (node (ref "IC2") (pin "16") (pinfunction "D1A_16") (pintype "bidirectional"))
      (node (ref "JP2") (pin "13") (pinfunction "13_13") (pintype "passive"))
    )
    (net (code "129") (name "Net-(IC2-D1B)") (class "Default")
      (node (ref "IC2") (pin "17") (pinfunction "D1B_17") (pintype "bidirectional"))
      (node (ref "JP2") (pin "14") (pinfunction "14_14") (pintype "passive"))
    )
    (net (code "130") (name "Net-(IC2-D2A)") (class "Default")
      (node (ref "IC2") (pin "18") (pinfunction "D2A_18") (pintype "bidirectional"))
      (node (ref "JP2") (pin "15") (pinfunction "15_15") (pintype "passive"))
    )
    (net (code "131") (name "Net-(IC2-D2B)") (class "Default")
      (node (ref "IC2") (pin "19") (pinfunction "D2B_19") (pintype "bidirectional"))
      (node (ref "JP2") (pin "16") (pinfunction "16_16") (pintype "passive"))
    )
    (net (code "132") (name "Net-(IC3-A1A)") (class "Default")
      (node (ref "IC3") (pin "1") (pinfunction "A1A_1") (pintype "bidirectional"))
      (node (ref "JP3") (pin "1") (pinfunction "1_1") (pintype "passive"))
    )
    (net (code "133") (name "Net-(IC3-A1B)") (class "Default")
      (node (ref "IC3") (pin "2") (pinfunction "A1B_2") (pintype "bidirectional"))
      (node (ref "JP3") (pin "2") (pinfunction "2_2") (pintype "passive"))
    )
    (net (code "134") (name "Net-(IC3-A2A)") (class "Default")
      (node (ref "IC3") (pin "3") (pinfunction "A2A_3") (pintype "bidirectional"))
      (node (ref "JP3") (pin "3") (pinfunction "3_3") (pintype "passive"))
    )
    (net (code "135") (name "Net-(IC3-A2B)") (class "Default")
      (node (ref "IC3") (pin "4") (pinfunction "A2B_4") (pintype "bidirectional"))
      (node (ref "JP3") (pin "4") (pinfunction "4_4") (pintype "passive"))
    )
    (net (code "136") (name "Net-(IC3-B1A)") (class "Default")
      (node (ref "IC3") (pin "6") (pinfunction "B1A_6") (pintype "bidirectional"))
      (node (ref "JP3") (pin "5") (pinfunction "5_5") (pintype "passive"))
    )
    (net (code "137") (name "Net-(IC3-B1B)") (class "Default")
      (node (ref "IC3") (pin "7") (pinfunction "B1B_7") (pintype "bidirectional"))
      (node (ref "JP3") (pin "6") (pinfunction "6_6") (pintype "passive"))
    )
    (net (code "138") (name "Net-(IC3-B2A)") (class "Default")
      (node (ref "IC3") (pin "8") (pinfunction "B2A_8") (pintype "bidirectional"))
      (node (ref "JP3") (pin "7") (pinfunction "7_7") (pintype "passive"))
    )
    (net (code "139") (name "Net-(IC3-B2B)") (class "Default")
      (node (ref "IC3") (pin "9") (pinfunction "B2B_9") (pintype "bidirectional"))
      (node (ref "JP3") (pin "8") (pinfunction "8_8") (pintype "passive"))
    )
    (net (code "140") (name "Net-(IC3-C1A)") (class "Default")
      (node (ref "IC3") (pin "11") (pinfunction "C1A_11") (pintype "bidirectional"))
      (node (ref "JP3") (pin "9") (pinfunction "9_9") (pintype "passive"))
    )
    (net (code "141") (name "Net-(IC3-C1B)") (class "Default")
      (node (ref "IC3") (pin "12") (pinfunction "C1B_12") (pintype "bidirectional"))
      (node (ref "JP3") (pin "10") (pinfunction "10_10") (pintype "passive"))
    )
    (net (code "142") (name "Net-(IC3-C2A)") (class "Default")
      (node (ref "IC3") (pin "13") (pinfunction "C2A_13") (pintype "bidirectional"))
      (node (ref "JP3") (pin "11") (pinfunction "11_11") (pintype "passive"))
    )
    (net (code "143") (name "Net-(IC3-C2B)") (class "Default")
      (node (ref "IC3") (pin "14") (pinfunction "C2B_14") (pintype "bidirectional"))
      (node (ref "JP3") (pin "12") (pinfunction "12_12") (pintype "passive"))
    )
    (net (code "144") (name "Net-(IC3-D1A)") (class "Default")
      (node (ref "IC3") (pin "16") (pinfunction "D1A_16") (pintype "bidirectional"))
      (node (ref "JP3") (pin "13") (pinfunction "13_13") (pintype "passive"))
    )
    (net (code "145") (name "Net-(IC3-D1B)") (class "Default")
      (node (ref "IC3") (pin "17") (pinfunction "D1B_17") (pintype "bidirectional"))
      (node (ref "JP3") (pin "14") (pinfunction "14_14") (pintype "passive"))
    )
    (net (code "146") (name "Net-(IC3-D2A)") (class "Default")
      (node (ref "IC3") (pin "18") (pinfunction "D2A_18") (pintype "bidirectional"))
      (node (ref "JP3") (pin "15") (pinfunction "15_15") (pintype "passive"))
    )
    (net (code "147") (name "Net-(IC3-D2B)") (class "Default")
      (node (ref "IC3") (pin "19") (pinfunction "D2B_19") (pintype "bidirectional"))
      (node (ref "JP3") (pin "16") (pinfunction "16_16") (pintype "passive"))
    )
    (net (code "148") (name "Net-(IC4-A1A)") (class "Default")
      (node (ref "IC4") (pin "1") (pinfunction "A1A_1") (pintype "bidirectional"))
      (node (ref "JP4") (pin "1") (pinfunction "1_1") (pintype "passive"))
    )
    (net (code "149") (name "Net-(IC4-A1B)") (class "Default")
      (node (ref "IC4") (pin "2") (pinfunction "A1B_2") (pintype "bidirectional"))
      (node (ref "JP4") (pin "2") (pinfunction "2_2") (pintype "passive"))
    )
    (net (code "150") (name "Net-(IC4-A2A)") (class "Default")
      (node (ref "IC4") (pin "3") (pinfunction "A2A_3") (pintype "bidirectional"))
      (node (ref "JP4") (pin "3") (pinfunction "3_3") (pintype "passive"))
    )
    (net (code "151") (name "Net-(IC4-A2B)") (class "Default")
      (node (ref "IC4") (pin "4") (pinfunction "A2B_4") (pintype "bidirectional"))
      (node (ref "JP4") (pin "4") (pinfunction "4_4") (pintype "passive"))
    )
    (net (code "152") (name "Net-(IC4-B1A)") (class "Default")
      (node (ref "IC4") (pin "6") (pinfunction "B1A_6") (pintype "bidirectional"))
      (node (ref "JP4") (pin "5") (pinfunction "5_5") (pintype "passive"))
    )
    (net (code "153") (name "Net-(IC4-B1B)") (class "Default")
      (node (ref "IC4") (pin "7") (pinfunction "B1B_7") (pintype "bidirectional"))
      (node (ref "JP4") (pin "6") (pinfunction "6_6") (pintype "passive"))
    )
    (net (code "154") (name "Net-(IC4-B2A)") (class "Default")
      (node (ref "IC4") (pin "8") (pinfunction "B2A_8") (pintype "bidirectional"))
      (node (ref "JP4") (pin "7") (pinfunction "7_7") (pintype "passive"))
    )
    (net (code "155") (name "Net-(IC4-B2B)") (class "Default")
      (node (ref "IC4") (pin "9") (pinfunction "B2B_9") (pintype "bidirectional"))
      (node (ref "JP4") (pin "8") (pinfunction "8_8") (pintype "passive"))
    )
    (net (code "156") (name "Net-(IC4-C1A)") (class "Default")
      (node (ref "IC4") (pin "11") (pinfunction "C1A_11") (pintype "bidirectional"))
      (node (ref "JP4") (pin "9") (pinfunction "9_9") (pintype "passive"))
    )
    (net (code "157") (name "Net-(IC4-C1B)") (class "Default")
      (node (ref "IC4") (pin "12") (pinfunction "C1B_12") (pintype "bidirectional"))
      (node (ref "JP4") (pin "10") (pinfunction "10_10") (pintype "passive"))
    )
    (net (code "158") (name "Net-(IC4-C2A)") (class "Default")
      (node (ref "IC4") (pin "13") (pinfunction "C2A_13") (pintype "bidirectional"))
      (node (ref "JP4") (pin "11") (pinfunction "11_11") (pintype "passive"))
    )
    (net (code "159") (name "Net-(IC4-C2B)") (class "Default")
      (node (ref "IC4") (pin "14") (pinfunction "C2B_14") (pintype "bidirectional"))
      (node (ref "JP4") (pin "12") (pinfunction "12_12") (pintype "passive"))
    )
    (net (code "160") (name "Net-(IC4-D1A)") (class "Default")
      (node (ref "IC4") (pin "16") (pinfunction "D1A_16") (pintype "bidirectional"))
      (node (ref "JP4") (pin "13") (pinfunction "13_13") (pintype "passive"))
    )
    (net (code "161") (name "Net-(IC4-D1B)") (class "Default")
      (node (ref "IC4") (pin "17") (pinfunction "D1B_17") (pintype "bidirectional"))
      (node (ref "JP4") (pin "14") (pinfunction "14_14") (pintype "passive"))
    )
    (net (code "162") (name "Net-(IC4-D2A)") (class "Default")
      (node (ref "IC4") (pin "18") (pinfunction "D2A_18") (pintype "bidirectional"))
      (node (ref "JP4") (pin "15") (pinfunction "15_15") (pintype "passive"))
    )
    (net (code "163") (name "Net-(IC4-D2B)") (class "Default")
      (node (ref "IC4") (pin "19") (pinfunction "D2B_19") (pintype "bidirectional"))
      (node (ref "JP4") (pin "16") (pinfunction "16_16") (pintype "passive"))
    )
    (net (code "164") (name "Net-(IC5-A1A)") (class "Default")
      (node (ref "IC5") (pin "1") (pinfunction "A1A_1") (pintype "bidirectional"))
      (node (ref "JP5") (pin "1") (pinfunction "1_1") (pintype "passive"))
    )
    (net (code "165") (name "Net-(IC5-A1B)") (class "Default")
      (node (ref "IC5") (pin "2") (pinfunction "A1B_2") (pintype "bidirectional"))
      (node (ref "JP5") (pin "2") (pinfunction "2_2") (pintype "passive"))
    )
    (net (code "166") (name "Net-(IC5-A2A)") (class "Default")
      (node (ref "IC5") (pin "3") (pinfunction "A2A_3") (pintype "bidirectional"))
      (node (ref "JP5") (pin "3") (pinfunction "3_3") (pintype "passive"))
    )
    (net (code "167") (name "Net-(IC5-A2B)") (class "Default")
      (node (ref "IC5") (pin "4") (pinfunction "A2B_4") (pintype "bidirectional"))
      (node (ref "JP5") (pin "4") (pinfunction "4_4") (pintype "passive"))
    )
    (net (code "168") (name "Net-(IC5-B1A)") (class "Default")
      (node (ref "IC5") (pin "6") (pinfunction "B1A_6") (pintype "bidirectional"))
      (node (ref "JP5") (pin "5") (pinfunction "5_5") (pintype "passive"))
    )
    (net (code "169") (name "Net-(IC5-B1B)") (class "Default")
      (node (ref "IC5") (pin "7") (pinfunction "B1B_7") (pintype "bidirectional"))
      (node (ref "JP5") (pin "6") (pinfunction "6_6") (pintype "passive"))
    )
    (net (code "170") (name "Net-(IC5-B2A)") (class "Default")
      (node (ref "IC5") (pin "8") (pinfunction "B2A_8") (pintype "bidirectional"))
      (node (ref "JP5") (pin "7") (pinfunction "7_7") (pintype "passive"))
    )
    (net (code "171") (name "Net-(IC5-B2B)") (class "Default")
      (node (ref "IC5") (pin "9") (pinfunction "B2B_9") (pintype "bidirectional"))
      (node (ref "JP5") (pin "8") (pinfunction "8_8") (pintype "passive"))
    )
    (net (code "172") (name "Net-(IC5-C1A)") (class "Default")
      (node (ref "IC5") (pin "11") (pinfunction "C1A_11") (pintype "bidirectional"))
      (node (ref "JP5") (pin "9") (pinfunction "9_9") (pintype "passive"))
    )
    (net (code "173") (name "Net-(IC5-C1B)") (class "Default")
      (node (ref "IC5") (pin "12") (pinfunction "C1B_12") (pintype "bidirectional"))
      (node (ref "JP5") (pin "10") (pinfunction "10_10") (pintype "passive"))
    )
    (net (code "174") (name "Net-(IC5-C2A)") (class "Default")
      (node (ref "IC5") (pin "13") (pinfunction "C2A_13") (pintype "bidirectional"))
      (node (ref "JP5") (pin "11") (pinfunction "11_11") (pintype "passive"))
    )
    (net (code "175") (name "Net-(IC5-C2B)") (class "Default")
      (node (ref "IC5") (pin "14") (pinfunction "C2B_14") (pintype "bidirectional"))
      (node (ref "JP5") (pin "12") (pinfunction "12_12") (pintype "passive"))
    )
    (net (code "176") (name "Net-(IC5-D1A)") (class "Default")
      (node (ref "IC5") (pin "16") (pinfunction "D1A_16") (pintype "bidirectional"))
      (node (ref "JP5") (pin "13") (pinfunction "13_13") (pintype "passive"))
    )
    (net (code "177") (name "Net-(IC5-D1B)") (class "Default")
      (node (ref "IC5") (pin "17") (pinfunction "D1B_17") (pintype "bidirectional"))
      (node (ref "JP5") (pin "14") (pinfunction "14_14") (pintype "passive"))
    )
    (net (code "178") (name "Net-(IC5-D2A)") (class "Default")
      (node (ref "IC5") (pin "18") (pinfunction "D2A_18") (pintype "bidirectional"))
      (node (ref "JP5") (pin "15") (pinfunction "15_15") (pintype "passive"))
    )
    (net (code "179") (name "Net-(IC5-D2B)") (class "Default")
      (node (ref "IC5") (pin "19") (pinfunction "D2B_19") (pintype "bidirectional"))
      (node (ref "JP5") (pin "16") (pinfunction "16_16") (pintype "passive"))
    )
    (net (code "180") (name "Net-(IC6-A1A)") (class "Default")
      (node (ref "IC6") (pin "1") (pinfunction "A1A_1") (pintype "bidirectional"))
      (node (ref "JP6") (pin "1") (pinfunction "1_1") (pintype "passive"))
    )
    (net (code "181") (name "Net-(IC6-A1B)") (class "Default")
      (node (ref "IC6") (pin "2") (pinfunction "A1B_2") (pintype "bidirectional"))
      (node (ref "JP6") (pin "2") (pinfunction "2_2") (pintype "passive"))
    )
    (net (code "182") (name "Net-(IC6-A2A)") (class "Default")
      (node (ref "IC6") (pin "3") (pinfunction "A2A_3") (pintype "bidirectional"))
      (node (ref "JP6") (pin "3") (pinfunction "3_3") (pintype "passive"))
    )
    (net (code "183") (name "Net-(IC6-A2B)") (class "Default")
      (node (ref "IC6") (pin "4") (pinfunction "A2B_4") (pintype "bidirectional"))
      (node (ref "JP6") (pin "4") (pinfunction "4_4") (pintype "passive"))
    )
    (net (code "184") (name "Net-(IC6-B1A)") (class "Default")
      (node (ref "IC6") (pin "6") (pinfunction "B1A_6") (pintype "bidirectional"))
      (node (ref "JP6") (pin "5") (pinfunction "5_5") (pintype "passive"))
    )
    (net (code "185") (name "Net-(IC6-B1B)") (class "Default")
      (node (ref "IC6") (pin "7") (pinfunction "B1B_7") (pintype "bidirectional"))
      (node (ref "JP6") (pin "6") (pinfunction "6_6") (pintype "passive"))
    )
    (net (code "186") (name "Net-(IC6-B2A)") (class "Default")
      (node (ref "IC6") (pin "8") (pinfunction "B2A_8") (pintype "bidirectional"))
      (node (ref "JP6") (pin "7") (pinfunction "7_7") (pintype "passive"))
    )
    (net (code "187") (name "Net-(IC6-B2B)") (class "Default")
      (node (ref "IC6") (pin "9") (pinfunction "B2B_9") (pintype "bidirectional"))
      (node (ref "JP6") (pin "8") (pinfunction "8_8") (pintype "passive"))
    )
    (net (code "188") (name "Net-(IC6-C1A)") (class "Default")
      (node (ref "IC6") (pin "11") (pinfunction "C1A_11") (pintype "bidirectional"))
      (node (ref "JP6") (pin "9") (pinfunction "9_9") (pintype "passive"))
    )
    (net (code "189") (name "Net-(IC6-C1B)") (class "Default")
      (node (ref "IC6") (pin "12") (pinfunction "C1B_12") (pintype "bidirectional"))
      (node (ref "JP6") (pin "10") (pinfunction "10_10") (pintype "passive"))
    )
    (net (code "190") (name "Net-(IC6-C2A)") (class "Default")
      (node (ref "IC6") (pin "13") (pinfunction "C2A_13") (pintype "bidirectional"))
      (node (ref "JP6") (pin "11") (pinfunction "11_11") (pintype "passive"))
    )
    (net (code "191") (name "Net-(IC6-C2B)") (class "Default")
      (node (ref "IC6") (pin "14") (pinfunction "C2B_14") (pintype "bidirectional"))
      (node (ref "JP6") (pin "12") (pinfunction "12_12") (pintype "passive"))
    )
    (net (code "192") (name "Net-(IC6-D1A)") (class "Default")
      (node (ref "IC6") (pin "16") (pinfunction "D1A_16") (pintype "bidirectional"))
      (node (ref "JP6") (pin "13") (pinfunction "13_13") (pintype "passive"))
    )
    (net (code "193") (name "Net-(IC6-D1B)") (class "Default")
      (node (ref "IC6") (pin "17") (pinfunction "D1B_17") (pintype "bidirectional"))
      (node (ref "JP6") (pin "14") (pinfunction "14_14") (pintype "passive"))
    )
    (net (code "194") (name "Net-(IC6-D2A)") (class "Default")
      (node (ref "IC6") (pin "18") (pinfunction "D2A_18") (pintype "bidirectional"))
      (node (ref "JP6") (pin "15") (pinfunction "15_15") (pintype "passive"))
    )
    (net (code "195") (name "Net-(IC6-D2B)") (class "Default")
      (node (ref "IC6") (pin "19") (pinfunction "D2B_19") (pintype "bidirectional"))
      (node (ref "JP6") (pin "16") (pinfunction "16_16") (pintype "passive"))
    )
    (net (code "196") (name "Net-(IC7-A1A)") (class "Default")
      (node (ref "IC7") (pin "1") (pinfunction "A1A_1") (pintype "bidirectional"))
      (node (ref "JP7") (pin "1") (pinfunction "1_1") (pintype "passive"))
    )
    (net (code "197") (name "Net-(IC7-A1B)") (class "Default")
      (node (ref "IC7") (pin "2") (pinfunction "A1B_2") (pintype "bidirectional"))
      (node (ref "JP7") (pin "2") (pinfunction "2_2") (pintype "passive"))
    )
    (net (code "198") (name "Net-(IC7-A2A)") (class "Default")
      (node (ref "IC7") (pin "3") (pinfunction "A2A_3") (pintype "bidirectional"))
      (node (ref "JP7") (pin "3") (pinfunction "3_3") (pintype "passive"))
    )
    (net (code "199") (name "Net-(IC7-A2B)") (class "Default")
      (node (ref "IC7") (pin "4") (pinfunction "A2B_4") (pintype "bidirectional"))
      (node (ref "JP7") (pin "4") (pinfunction "4_4") (pintype "passive"))
    )
    (net (code "200") (name "Net-(IC7-B1A)") (class "Default")
      (node (ref "IC7") (pin "6") (pinfunction "B1A_6") (pintype "bidirectional"))
      (node (ref "JP7") (pin "5") (pinfunction "5_5") (pintype "passive"))
    )
    (net (code "201") (name "Net-(IC7-B1B)") (class "Default")
      (node (ref "IC7") (pin "7") (pinfunction "B1B_7") (pintype "bidirectional"))
      (node (ref "JP7") (pin "6") (pinfunction "6_6") (pintype "passive"))
    )
    (net (code "202") (name "Net-(IC7-B2A)") (class "Default")
      (node (ref "IC7") (pin "8") (pinfunction "B2A_8") (pintype "bidirectional"))
      (node (ref "JP7") (pin "7") (pinfunction "7_7") (pintype "passive"))
    )
    (net (code "203") (name "Net-(IC7-B2B)") (class "Default")
      (node (ref "IC7") (pin "9") (pinfunction "B2B_9") (pintype "bidirectional"))
      (node (ref "JP7") (pin "8") (pinfunction "8_8") (pintype "passive"))
    )
    (net (code "204") (name "Net-(IC7-C1A)") (class "Default")
      (node (ref "IC7") (pin "11") (pinfunction "C1A_11") (pintype "bidirectional"))
      (node (ref "JP7") (pin "9") (pinfunction "9_9") (pintype "passive"))
    )
    (net (code "205") (name "Net-(IC7-C1B)") (class "Default")
      (node (ref "IC7") (pin "12") (pinfunction "C1B_12") (pintype "bidirectional"))
      (node (ref "JP7") (pin "10") (pinfunction "10_10") (pintype "passive"))
    )
    (net (code "206") (name "Net-(IC7-C2A)") (class "Default")
      (node (ref "IC7") (pin "13") (pinfunction "C2A_13") (pintype "bidirectional"))
      (node (ref "JP7") (pin "11") (pinfunction "11_11") (pintype "passive"))
    )
    (net (code "207") (name "Net-(IC7-C2B)") (class "Default")
      (node (ref "IC7") (pin "14") (pinfunction "C2B_14") (pintype "bidirectional"))
      (node (ref "JP7") (pin "12") (pinfunction "12_12") (pintype "passive"))
    )
    (net (code "208") (name "Net-(IC7-D1A)") (class "Default")
      (node (ref "IC7") (pin "16") (pinfunction "D1A_16") (pintype "bidirectional"))
      (node (ref "JP7") (pin "13") (pinfunction "13_13") (pintype "passive"))
    )
    (net (code "209") (name "Net-(IC7-D1B)") (class "Default")
      (node (ref "IC7") (pin "17") (pinfunction "D1B_17") (pintype "bidirectional"))
      (node (ref "JP7") (pin "14") (pinfunction "14_14") (pintype "passive"))
    )
    (net (code "210") (name "Net-(IC7-D2A)") (class "Default")
      (node (ref "IC7") (pin "18") (pinfunction "D2A_18") (pintype "bidirectional"))
      (node (ref "JP7") (pin "15") (pinfunction "15_15") (pintype "passive"))
    )
    (net (code "211") (name "Net-(IC7-D2B)") (class "Default")
      (node (ref "IC7") (pin "19") (pinfunction "D2B_19") (pintype "bidirectional"))
      (node (ref "JP7") (pin "16") (pinfunction "16_16") (pintype "passive"))
    )
    (net (code "212") (name "Net-(IC8-A1A)") (class "Default")
      (node (ref "IC8") (pin "1") (pinfunction "A1A_1") (pintype "bidirectional"))
      (node (ref "JP8") (pin "1") (pinfunction "1_1") (pintype "passive"))
    )
    (net (code "213") (name "Net-(IC8-A1B)") (class "Default")
      (node (ref "IC8") (pin "2") (pinfunction "A1B_2") (pintype "bidirectional"))
      (node (ref "JP8") (pin "2") (pinfunction "2_2") (pintype "passive"))
    )
    (net (code "214") (name "Net-(IC8-A2A)") (class "Default")
      (node (ref "IC8") (pin "3") (pinfunction "A2A_3") (pintype "bidirectional"))
      (node (ref "JP8") (pin "3") (pinfunction "3_3") (pintype "passive"))
    )
    (net (code "215") (name "Net-(IC8-A2B)") (class "Default")
      (node (ref "IC8") (pin "4") (pinfunction "A2B_4") (pintype "bidirectional"))
      (node (ref "JP8") (pin "4") (pinfunction "4_4") (pintype "passive"))
    )
    (net (code "216") (name "Net-(IC8-B1A)") (class "Default")
      (node (ref "IC8") (pin "6") (pinfunction "B1A_6") (pintype "bidirectional"))
      (node (ref "JP8") (pin "5") (pinfunction "5_5") (pintype "passive"))
    )
    (net (code "217") (name "Net-(IC8-B1B)") (class "Default")
      (node (ref "IC8") (pin "7") (pinfunction "B1B_7") (pintype "bidirectional"))
      (node (ref "JP8") (pin "6") (pinfunction "6_6") (pintype "passive"))
    )
    (net (code "218") (name "Net-(IC8-B2A)") (class "Default")
      (node (ref "IC8") (pin "8") (pinfunction "B2A_8") (pintype "bidirectional"))
      (node (ref "JP8") (pin "7") (pinfunction "7_7") (pintype "passive"))
    )
    (net (code "219") (name "Net-(IC8-B2B)") (class "Default")
      (node (ref "IC8") (pin "9") (pinfunction "B2B_9") (pintype "bidirectional"))
      (node (ref "JP8") (pin "8") (pinfunction "8_8") (pintype "passive"))
    )
    (net (code "220") (name "Net-(IC8-C1A)") (class "Default")
      (node (ref "IC8") (pin "11") (pinfunction "C1A_11") (pintype "bidirectional"))
      (node (ref "JP8") (pin "9") (pinfunction "9_9") (pintype "passive"))
    )
    (net (code "221") (name "Net-(IC8-C1B)") (class "Default")
      (node (ref "IC8") (pin "12") (pinfunction "C1B_12") (pintype "bidirectional"))
      (node (ref "JP8") (pin "10") (pinfunction "10_10") (pintype "passive"))
    )
    (net (code "222") (name "Net-(IC8-C2A)") (class "Default")
      (node (ref "IC8") (pin "13") (pinfunction "C2A_13") (pintype "bidirectional"))
      (node (ref "JP8") (pin "11") (pinfunction "11_11") (pintype "passive"))
    )
    (net (code "223") (name "Net-(IC8-C2B)") (class "Default")
      (node (ref "IC8") (pin "14") (pinfunction "C2B_14") (pintype "bidirectional"))
      (node (ref "JP8") (pin "12") (pinfunction "12_12") (pintype "passive"))
    )
    (net (code "224") (name "Net-(IC8-D1A)") (class "Default")
      (node (ref "IC8") (pin "16") (pinfunction "D1A_16") (pintype "bidirectional"))
      (node (ref "JP8") (pin "13") (pinfunction "13_13") (pintype "passive"))
    )
    (net (code "225") (name "Net-(IC8-D1B)") (class "Default")
      (node (ref "IC8") (pin "17") (pinfunction "D1B_17") (pintype "bidirectional"))
      (node (ref "JP8") (pin "14") (pinfunction "14_14") (pintype "passive"))
    )
    (net (code "226") (name "Net-(IC8-D2A)") (class "Default")
      (node (ref "IC8") (pin "18") (pinfunction "D2A_18") (pintype "bidirectional"))
      (node (ref "JP8") (pin "15") (pinfunction "15_15") (pintype "passive"))
    )
    (net (code "227") (name "Net-(IC8-D2B)") (class "Default")
      (node (ref "IC8") (pin "19") (pinfunction "D2B_19") (pintype "bidirectional"))
      (node (ref "JP8") (pin "16") (pinfunction "16_16") (pintype "passive"))
    )
    (net (code "228") (name "Net-(LED1-PadC)") (class "Default")
      (node (ref "LED1") (pin "C") (pinfunction "C_C") (pintype "passive"))
      (node (ref "R8") (pin "1") (pinfunction "1_1") (pintype "passive"))
    )
    (net (code "229") (name "Net-(LEDPOW-PadC)") (class "Default")
      (node (ref "LEDPOW") (pin "C") (pinfunction "C_C") (pintype "passive"))
      (node (ref "RLEDPOW") (pin "1") (pinfunction "1_1") (pintype "passive"))
    )
    (net (code "230") (name "Net-(LEDPOW1-PadC)") (class "Default")
      (node (ref "LEDPOW1") (pin "C") (pinfunction "C_C") (pintype "passive"))
      (node (ref "RLEDPOW1") (pin "1") (pinfunction "1_1") (pintype "passive"))
    )
    (net (code "231") (name "Net-(VSLUE-1Y1)") (class "Default")
      (node (ref "J14") (pin "1") (pinfunction "1_1") (pintype "passive"))
      (node (ref "OJ1") (pin "1") (pinfunction "1_1") (pintype "bidirectional"))
      (node (ref "VSLUE") (pin "16") (pinfunction "1Y2_16") (pintype "output"))
      (node (ref "VSLUE") (pin "18") (pinfunction "1Y1_18") (pintype "output"))
    )
    (net (code "232") (name "Net-(VSLUE-1Y3)") (class "Default")
      (node (ref "D11") (pin "1") (pinfunction "1_1") (pintype "passive"))
      (node (ref "OJ2") (pin "1") (pinfunction "1_1") (pintype "bidirectional"))
      (node (ref "VSLUE") (pin "12") (pinfunction "1Y4_12") (pintype "output"))
      (node (ref "VSLUE") (pin "14") (pinfunction "1Y3_14") (pintype "output"))
    )
    (net (code "233") (name "Net-(VSLUE-2Y1)") (class "Default")
      (node (ref "B11") (pin "1") (pinfunction "1_1") (pintype "passive"))
      (node (ref "OJ3") (pin "1") (pinfunction "1_1") (pintype "bidirectional"))
      (node (ref "VSLUE") (pin "7") (pinfunction "2Y2_7") (pintype "output"))
      (node (ref "VSLUE") (pin "9") (pinfunction "2Y1_9") (pintype "output"))
    )
    (net (code "234") (name "Net-(VSLUE-2Y3)") (class "Default")
      (node (ref "E10") (pin "1") (pinfunction "1_1") (pintype "passive"))
      (node (ref "OJ4") (pin "1") (pinfunction "1_1") (pintype "bidirectional"))
      (node (ref "VSLUE") (pin "3") (pinfunction "2Y4_3") (pintype "output"))
      (node (ref "VSLUE") (pin "5") (pinfunction "2Y3_5") (pintype "output"))
    )
    (net (code "235") (name "Net-(VSLUE6-1Y1)") (class "Default")
      (node (ref "D6") (pin "1") (pinfunction "1_1") (pintype "passive"))
      (node (ref "OJ52") (pin "1") (pinfunction "1_1") (pintype "bidirectional"))
      (node (ref "VSLUE6") (pin "16") (pinfunction "1Y2_16") (pintype "output"))
      (node (ref "VSLUE6") (pin "18") (pinfunction "1Y1_18") (pintype "output"))
    )
    (net (code "236") (name "Net-(VSLUE6-1Y3)") (class "Default")
      (node (ref "C6") (pin "1") (pinfunction "1_1") (pintype "passive"))
      (node (ref "OJ51") (pin "1") (pinfunction "1_1") (pintype "bidirectional"))
      (node (ref "VSLUE6") (pin "12") (pinfunction "1Y4_12") (pintype "output"))
      (node (ref "VSLUE6") (pin "14") (pinfunction "1Y3_14") (pintype "output"))
    )
    (net (code "237") (name "Net-(VSLUE6-2Y1)") (class "Default")
      (node (ref "E6") (pin "1") (pinfunction "1_1") (pintype "passive"))
      (node (ref "OJ50") (pin "1") (pinfunction "1_1") (pintype "bidirectional"))
      (node (ref "VSLUE6") (pin "7") (pinfunction "2Y2_7") (pintype "output"))
      (node (ref "VSLUE6") (pin "9") (pinfunction "2Y1_9") (pintype "output"))
    )
    (net (code "238") (name "Net-(VSLUE6-2Y3)") (class "Default")
      (node (ref "C8") (pin "1") (pinfunction "1_1") (pintype "passive"))
      (node (ref "OJ49") (pin "1") (pinfunction "1_1") (pintype "bidirectional"))
      (node (ref "VSLUE6") (pin "3") (pinfunction "2Y4_3") (pintype "output"))
      (node (ref "VSLUE6") (pin "5") (pinfunction "2Y3_5") (pintype "output"))
    )
    (net (code "239") (name "Net-(VSLUE8-1Y1)") (class "Default")
      (node (ref "B5") (pin "1") (pinfunction "1_1") (pintype "passive"))
      (node (ref "OJ68") (pin "1") (pinfunction "1_1") (pintype "bidirectional"))
      (node (ref "VSLUE8") (pin "16") (pinfunction "1Y2_16") (pintype "output"))
      (node (ref "VSLUE8") (pin "18") (pinfunction "1Y1_18") (pintype "output"))
    )
    (net (code "240") (name "Net-(VSLUE8-1Y3)") (class "Default")
      (node (ref "A5") (pin "1") (pinfunction "1_1") (pintype "passive"))
      (node (ref "OJ67") (pin "1") (pinfunction "1_1") (pintype "bidirectional"))
      (node (ref "VSLUE8") (pin "12") (pinfunction "1Y4_12") (pintype "output"))
      (node (ref "VSLUE8") (pin "14") (pinfunction "1Y3_14") (pintype "output"))
    )
    (net (code "241") (name "Net-(VSLUE8-2Y1)") (class "Default")
      (node (ref "N14") (pin "1") (pinfunction "1_1") (pintype "passive"))
      (node (ref "OJ66") (pin "1") (pinfunction "1_1") (pintype "bidirectional"))
      (node (ref "VSLUE8") (pin "7") (pinfunction "2Y2_7") (pintype "output"))
      (node (ref "VSLUE8") (pin "9") (pinfunction "2Y1_9") (pintype "output"))
    )
    (net (code "242") (name "Net-(VSLUE8-2Y3)") (class "Default")
      (node (ref "D5") (pin "1") (pinfunction "1_1") (pintype "passive"))
      (node (ref "OJ65") (pin "1") (pinfunction "1_1") (pintype "bidirectional"))
      (node (ref "VSLUE8") (pin "3") (pinfunction "2Y4_3") (pintype "output"))
      (node (ref "VSLUE8") (pin "5") (pinfunction "2Y3_5") (pintype "output"))
    )
    (net (code "243") (name "Net-(VSLUE11-1Y1)") (class "Default")
      (node (ref "D12") (pin "1") (pinfunction "1_1") (pintype "passive"))
      (node (ref "OJ92") (pin "1") (pinfunction "1_1") (pintype "bidirectional"))
      (node (ref "VSLUE11") (pin "16") (pinfunction "1Y2_16") (pintype "output"))
      (node (ref "VSLUE11") (pin "18") (pinfunction "1Y1_18") (pintype "output"))
    )
    (net (code "244") (name "Net-(VSLUE11-1Y3)") (class "Default")
      (node (ref "B3") (pin "1") (pinfunction "1_1") (pintype "passive"))
      (node (ref "OJ91") (pin "1") (pinfunction "1_1") (pintype "bidirectional"))
      (node (ref "VSLUE11") (pin "12") (pinfunction "1Y4_12") (pintype "output"))
      (node (ref "VSLUE11") (pin "14") (pinfunction "1Y3_14") (pintype "output"))
    )
    (net (code "245") (name "Net-(VSLUE11-2Y1)") (class "Default")
      (node (ref "B4") (pin "1") (pinfunction "1_1") (pintype "passive"))
      (node (ref "OJ90") (pin "1") (pinfunction "1_1") (pintype "bidirectional"))
      (node (ref "VSLUE11") (pin "7") (pinfunction "2Y2_7") (pintype "output"))
      (node (ref "VSLUE11") (pin "9") (pinfunction "2Y1_9") (pintype "output"))
    )
    (net (code "246") (name "Net-(VSLUE11-2Y3)") (class "Default")
      (node (ref "A4") (pin "1") (pinfunction "1_1") (pintype "passive"))
      (node (ref "OJ89") (pin "1") (pinfunction "1_1") (pintype "bidirectional"))
      (node (ref "VSLUE11") (pin "3") (pinfunction "2Y4_3") (pintype "output"))
      (node (ref "VSLUE11") (pin "5") (pinfunction "2Y3_5") (pintype "output"))
    )
    (net (code "247") (name "unconnected-(J2-Pad1)") (class "Default")
      (node (ref "J2") (pin "1") (pinfunction "1_1") (pintype "passive"))
    )
    (net (code "248") (name "unconnected-(J2-Pad2)") (class "Default")
      (node (ref "J2") (pin "2") (pinfunction "2_2") (pintype "passive"))
    )
    (net (code "249") (name "unconnected-(J2-Pad3)") (class "Default")
      (node (ref "J2") (pin "3") (pinfunction "3_3") (pintype "passive"))
    )
    (net (code "250") (name "unconnected-(J2-Pad4)") (class "Default")
      (node (ref "J2") (pin "4") (pinfunction "4_4") (pintype "passive"))
    )
    (net (code "251") (name "unconnected-(J2-Pad5)") (class "Default")
      (node (ref "J2") (pin "5") (pinfunction "5_5") (pintype "passive"))
    )
    (net (code "252") (name "unconnected-(J2-Pad6)") (class "Default")
      (node (ref "J2") (pin "6") (pinfunction "6_6") (pintype "passive"))
    )
    (net (code "253") (name "unconnected-(J2-Pad7)") (class "Default")
      (node (ref "J2") (pin "7") (pinfunction "7_7") (pintype "passive"))
    )
    (net (code "254") (name "unconnected-(J2-Pad8)") (class "Default")
      (node (ref "J2") (pin "8") (pinfunction "8_8") (pintype "passive"))
    )
    (net (code "255") (name "unconnected-(J2-Pad9)") (class "Default")
      (node (ref "J2") (pin "9") (pinfunction "9_9") (pintype "passive"))
    )
    (net (code "256") (name "unconnected-(J2-Pad10)") (class "Default")
      (node (ref "J2") (pin "10") (pinfunction "10_10") (pintype "passive"))
    )
    (net (code "257") (name "unconnected-(J2-Pad11)") (class "Default")
      (node (ref "J2") (pin "11") (pinfunction "11_11") (pintype "passive"))
    )
    (net (code "258") (name "unconnected-(J2-Pad12)") (class "Default")
      (node (ref "J2") (pin "12") (pinfunction "12_12") (pintype "passive"))
    )
    (net (code "259") (name "unconnected-(J2-Pad13)") (class "Default")
      (node (ref "J2") (pin "13") (pinfunction "13_13") (pintype "passive"))
    )
    (net (code "260") (name "unconnected-(J2-Pad14)") (class "Default")
      (node (ref "J2") (pin "14") (pinfunction "14_14") (pintype "passive"))
    )
    (net (code "261") (name "unconnected-(J2-Pad15)") (class "Default")
      (node (ref "J2") (pin "15") (pinfunction "15_15") (pintype "passive"))
    )
    (net (code "262") (name "unconnected-(J2-Pad16)") (class "Default")
      (node (ref "J2") (pin "16") (pinfunction "16_16") (pintype "passive"))
    )
    (net (code "263") (name "unconnected-(J2-Pad17)") (class "Default")
      (node (ref "J2") (pin "17") (pinfunction "17_17") (pintype "passive"))
    )
    (net (code "264") (name "unconnected-(J2-Pad18)") (class "Default")
      (node (ref "J2") (pin "18") (pinfunction "18_18") (pintype "passive"))
    )
    (net (code "265") (name "unconnected-(J2-Pad19)") (class "Default")
      (node (ref "J2") (pin "19") (pinfunction "19_19") (pintype "passive"))
    )
    (net (code "266") (name "unconnected-(J2-Pad20)") (class "Default")
      (node (ref "J2") (pin "20") (pinfunction "20_20") (pintype "passive"))
    )
    (net (code "267") (name "unconnected-(J2-Pad21)") (class "Default")
      (node (ref "J2") (pin "21") (pinfunction "21_21") (pintype "passive"))
    )
    (net (code "268") (name "unconnected-(J2-Pad22)") (class "Default")
      (node (ref "J2") (pin "22") (pinfunction "22_22") (pintype "passive"))
    )
    (net (code "269") (name "unconnected-(J2-Pad23)") (class "Default")
      (node (ref "J2") (pin "23") (pinfunction "23_23") (pintype "passive"))
    )
    (net (code "270") (name "unconnected-(J2-Pad24)") (class "Default")
      (node (ref "J2") (pin "24") (pinfunction "24_24") (pintype "passive"))
    )
    (net (code "271") (name "unconnected-(J2-Pad25)") (class "Default")
      (node (ref "J2") (pin "25") (pinfunction "25_25") (pintype "passive"))
    )
    (net (code "272") (name "unconnected-(J2-Pad26)") (class "Default")
      (node (ref "J2") (pin "26") (pinfunction "26_26") (pintype "passive"))
    )
    (net (code "273") (name "unconnected-(J19A-MSV-Pad1-A1)") (class "Default")
      (node (ref "J19") (pin "1-A1") (pinfunction "MSV_1-A1") (pintype "passive"))
    )
    (net (code "274") (name "unconnected-(J19AA-MS-Pad1-A4)") (class "Default")
      (node (ref "J19") (pin "1-A4") (pinfunction "MS_1-A4") (pintype "passive"))
    )
    (net (code "275") (name "unconnected-(J19AB-MS-Pad1-A5)") (class "Default")
      (node (ref "J19") (pin "1-A5") (pinfunction "MS_1-A5") (pintype "passive"))
    )
    (net (code "276") (name "unconnected-(J19AC-MS-Pad1-A6)") (class "Default")
      (node (ref "J19") (pin "1-A6") (pinfunction "MS_1-A6") (pintype "passive"))
    )
    (net (code "277") (name "unconnected-(J19AD-MS-Pad1-A7)") (class "Default")
      (node (ref "J19") (pin "1-A7") (pinfunction "MS_1-A7") (pintype "passive"))
    )
    (net (code "278") (name "unconnected-(J19AE-MS-Pad1-A8)") (class "Default")
      (node (ref "J19") (pin "1-A8") (pinfunction "MS_1-A8") (pintype "passive"))
    )
    (net (code "279") (name "unconnected-(J19AG-MSV-Pad1-C1)") (class "Default")
      (node (ref "J19") (pin "1-C1") (pinfunction "MSV_1-C1") (pintype "passive"))
    )
    (net (code "280") (name "unconnected-(J19AH-MS-Pad1-C10)") (class "Default")
      (node (ref "J19") (pin "1-C10") (pinfunction "MS_1-C10") (pintype "passive"))
    )
    (net (code "281") (name "unconnected-(J19AI-MS-Pad1-C11)") (class "Default")
      (node (ref "J19") (pin "1-C11") (pinfunction "MS_1-C11") (pintype "passive"))
    )
    (net (code "282") (name "unconnected-(J19AJ-MS-Pad1-C12)") (class "Default")
      (node (ref "J19") (pin "1-C12") (pinfunction "MS_1-C12") (pintype "passive"))
    )
    (net (code "283") (name "unconnected-(J19AK-MS-Pad1-C13)") (class "Default")
      (node (ref "J19") (pin "1-C13") (pinfunction "MS_1-C13") (pintype "passive"))
    )
    (net (code "284") (name "unconnected-(J19AL-MS-Pad1-C14)") (class "Default")
      (node (ref "J19") (pin "1-C14") (pinfunction "MS_1-C14") (pintype "passive"))
    )
    (net (code "285") (name "unconnected-(J19AM-MS-Pad1-C15)") (class "Default")
      (node (ref "J19") (pin "1-C15") (pinfunction "MS_1-C15") (pintype "passive"))
    )
    (net (code "286") (name "unconnected-(J19AN-MS-Pad1-C16)") (class "Default")
      (node (ref "J19") (pin "1-C16") (pinfunction "MS_1-C16") (pintype "passive"))
    )
    (net (code "287") (name "unconnected-(J19AO-MS-Pad1-C17)") (class "Default")
      (node (ref "J19") (pin "1-C17") (pinfunction "MS_1-C17") (pintype "passive"))
    )
    (net (code "288") (name "unconnected-(J19AP-MS-Pad1-C18)") (class "Default")
      (node (ref "J19") (pin "1-C18") (pinfunction "MS_1-C18") (pintype "passive"))
    )
    (net (code "289") (name "unconnected-(J19AQ-MS-Pad1-C19)") (class "Default")
      (node (ref "J19") (pin "1-C19") (pinfunction "MS_1-C19") (pintype "passive"))
    )
    (net (code "290") (name "unconnected-(J19AR-MS-Pad1-C2)") (class "Default")
      (node (ref "J19") (pin "1-C2") (pinfunction "MS_1-C2") (pintype "passive"))
    )
    (net (code "291") (name "unconnected-(J19AS-MS-Pad1-C20)") (class "Default")
      (node (ref "J19") (pin "1-C20") (pinfunction "MS_1-C20") (pintype "passive"))
    )
    (net (code "292") (name "unconnected-(J19AT-MS-Pad1-C21)") (class "Default")
      (node (ref "J19") (pin "1-C21") (pinfunction "MS_1-C21") (pintype "passive"))
    )
    (net (code "293") (name "unconnected-(J19AU-MS-Pad1-C22)") (class "Default")
      (node (ref "J19") (pin "1-C22") (pinfunction "MS_1-C22") (pintype "passive"))
    )
    (net (code "294") (name "unconnected-(J19AV-MS-Pad1-C23)") (class "Default")
      (node (ref "J19") (pin "1-C23") (pinfunction "MS_1-C23") (pintype "passive"))
    )
    (net (code "295") (name "unconnected-(J19AW-MS-Pad1-C24)") (class "Default")
      (node (ref "J19") (pin "1-C24") (pinfunction "MS_1-C24") (pintype "passive"))
    )
    (net (code "296") (name "unconnected-(J19AX-MS-Pad1-C25)") (class "Default")
      (node (ref "J19") (pin "1-C25") (pinfunction "MS_1-C25") (pintype "passive"))
    )
    (net (code "297") (name "unconnected-(J19AY-MS-Pad1-C26)") (class "Default")
      (node (ref "J19") (pin "1-C26") (pinfunction "MS_1-C26") (pintype "passive"))
    )
    (net (code "298") (name "unconnected-(J19AZ-MS-Pad1-C27)") (class "Default")
      (node (ref "J19") (pin "1-C27") (pinfunction "MS_1-C27") (pintype "passive"))
    )
    (net (code "299") (name "unconnected-(J19B-MS-Pad1-A10)") (class "Default")
      (node (ref "J19") (pin "1-A10") (pinfunction "MS_1-A10") (pintype "passive"))
    )
    (net (code "300") (name "unconnected-(J19BA-MS-Pad1-C28)") (class "Default")
      (node (ref "J19") (pin "1-C28") (pinfunction "MS_1-C28") (pintype "passive"))
    )
    (net (code "301") (name "unconnected-(J19BB-MS-Pad1-C29)") (class "Default")
      (node (ref "J19") (pin "1-C29") (pinfunction "MS_1-C29") (pintype "passive"))
    )
    (net (code "302") (name "unconnected-(J19BC-MS-Pad1-C3)") (class "Default")
      (node (ref "J19") (pin "1-C3") (pinfunction "MS_1-C3") (pintype "passive"))
    )
    (net (code "303") (name "unconnected-(J19BD-MS-Pad1-C30)") (class "Default")
      (node (ref "J19") (pin "1-C30") (pinfunction "MS_1-C30") (pintype "passive"))
    )
    (net (code "304") (name "unconnected-(J19BE-MS-Pad1-C31)") (class "Default")
      (node (ref "J19") (pin "1-C31") (pinfunction "MS_1-C31") (pintype "passive"))
    )
    (net (code "305") (name "unconnected-(J19BG-MS-Pad1-C4)") (class "Default")
      (node (ref "J19") (pin "1-C4") (pinfunction "MS_1-C4") (pintype "passive"))
    )
    (net (code "306") (name "unconnected-(J19BH-MS-Pad1-C5)") (class "Default")
      (node (ref "J19") (pin "1-C5") (pinfunction "MS_1-C5") (pintype "passive"))
    )
    (net (code "307") (name "unconnected-(J19BI-MS-Pad1-C6)") (class "Default")
      (node (ref "J19") (pin "1-C6") (pinfunction "MS_1-C6") (pintype "passive"))
    )
    (net (code "308") (name "unconnected-(J19BJ-MS-Pad1-C7)") (class "Default")
      (node (ref "J19") (pin "1-C7") (pinfunction "MS_1-C7") (pintype "passive"))
    )
    (net (code "309") (name "unconnected-(J19BK-MS-Pad1-C8)") (class "Default")
      (node (ref "J19") (pin "1-C8") (pinfunction "MS_1-C8") (pintype "passive"))
    )
    (net (code "310") (name "unconnected-(J19BM-MSV-Pad2-A1)") (class "Default")
      (node (ref "J19") (pin "2-A1") (pinfunction "MSV_2-A1") (pintype "passive"))
    )
    (net (code "311") (name "unconnected-(J19BN-MS-Pad2-A10)") (class "Default")
      (node (ref "J19") (pin "2-A10") (pinfunction "MS_2-A10") (pintype "passive"))
    )
    (net (code "312") (name "unconnected-(J19BO-MS-Pad2-A11)") (class "Default")
      (node (ref "J19") (pin "2-A11") (pinfunction "MS_2-A11") (pintype "passive"))
    )
    (net (code "313") (name "unconnected-(J19BP-MS-Pad2-A12)") (class "Default")
      (node (ref "J19") (pin "2-A12") (pinfunction "MS_2-A12") (pintype "passive"))
    )
    (net (code "314") (name "unconnected-(J19BQ-MS-Pad2-A13)") (class "Default")
      (node (ref "J19") (pin "2-A13") (pinfunction "MS_2-A13") (pintype "passive"))
    )
    (net (code "315") (name "unconnected-(J19BR-MS-Pad2-A14)") (class "Default")
      (node (ref "J19") (pin "2-A14") (pinfunction "MS_2-A14") (pintype "passive"))
    )
    (net (code "316") (name "unconnected-(J19BS-MS-Pad2-A15)") (class "Default")
      (node (ref "J19") (pin "2-A15") (pinfunction "MS_2-A15") (pintype "passive"))
    )
    (net (code "317") (name "unconnected-(J19BT-MS-Pad2-A16)") (class "Default")
      (node (ref "J19") (pin "2-A16") (pinfunction "MS_2-A16") (pintype "passive"))
    )
    (net (code "318") (name "unconnected-(J19BU-MS-Pad2-A17)") (class "Default")
      (node (ref "J19") (pin "2-A17") (pinfunction "MS_2-A17") (pintype "passive"))
    )
    (net (code "319") (name "unconnected-(J19BV-MS-Pad2-A18)") (class "Default")
      (node (ref "J19") (pin "2-A18") (pinfunction "MS_2-A18") (pintype "passive"))
    )
    (net (code "320") (name "unconnected-(J19BW-MS-Pad2-A19)") (class "Default")
      (node (ref "J19") (pin "2-A19") (pinfunction "MS_2-A19") (pintype "passive"))
    )
    (net (code "321") (name "unconnected-(J19BX-MS-Pad2-A2)") (class "Default")
      (node (ref "J19") (pin "2-A2") (pinfunction "MS_2-A2") (pintype "passive"))
    )
    (net (code "322") (name "unconnected-(J19BY-MS-Pad2-A20)") (class "Default")
      (node (ref "J19") (pin "2-A20") (pinfunction "MS_2-A20") (pintype "passive"))
    )
    (net (code "323") (name "unconnected-(J19BZ-MS-Pad2-A21)") (class "Default")
      (node (ref "J19") (pin "2-A21") (pinfunction "MS_2-A21") (pintype "passive"))
    )
    (net (code "324") (name "unconnected-(J19C-MS-Pad1-A11)") (class "Default")
      (node (ref "J19") (pin "1-A11") (pinfunction "MS_1-A11") (pintype "passive"))
    )
    (net (code "325") (name "unconnected-(J19CA-MS-Pad2-A22)") (class "Default")
      (node (ref "J19") (pin "2-A22") (pinfunction "MS_2-A22") (pintype "passive"))
    )
    (net (code "326") (name "unconnected-(J19CB-MS-Pad2-A23)") (class "Default")
      (node (ref "J19") (pin "2-A23") (pinfunction "MS_2-A23") (pintype "passive"))
    )
    (net (code "327") (name "unconnected-(J19CC-MS-Pad2-A24)") (class "Default")
      (node (ref "J19") (pin "2-A24") (pinfunction "MS_2-A24") (pintype "passive"))
    )
    (net (code "328") (name "unconnected-(J19CD-MS-Pad2-A25)") (class "Default")
      (node (ref "J19") (pin "2-A25") (pinfunction "MS_2-A25") (pintype "passive"))
    )
    (net (code "329") (name "unconnected-(J19CE-MS-Pad2-A26)") (class "Default")
      (node (ref "J19") (pin "2-A26") (pinfunction "MS_2-A26") (pintype "passive"))
    )
    (net (code "330") (name "unconnected-(J19CF-MS-Pad2-A27)") (class "Default")
      (node (ref "J19") (pin "2-A27") (pinfunction "MS_2-A27") (pintype "passive"))
    )
    (net (code "331") (name "unconnected-(J19CG-MS-Pad2-A28)") (class "Default")
      (node (ref "J19") (pin "2-A28") (pinfunction "MS_2-A28") (pintype "passive"))
    )
    (net (code "332") (name "unconnected-(J19CH-MS-Pad2-A29)") (class "Default")
      (node (ref "J19") (pin "2-A29") (pinfunction "MS_2-A29") (pintype "passive"))
    )
    (net (code "333") (name "unconnected-(J19CI-MS-Pad2-A3)") (class "Default")
      (node (ref "J19") (pin "2-A3") (pinfunction "MS_2-A3") (pintype "passive"))
    )
    (net (code "334") (name "unconnected-(J19CJ-MS-Pad2-A30)") (class "Default")
      (node (ref "J19") (pin "2-A30") (pinfunction "MS_2-A30") (pintype "passive"))
    )
    (net (code "335") (name "unconnected-(J19CK-MS-Pad2-A31)") (class "Default")
      (node (ref "J19") (pin "2-A31") (pinfunction "MS_2-A31") (pintype "passive"))
    )
    (net (code "336") (name "unconnected-(J19CM-MS-Pad2-A4)") (class "Default")
      (node (ref "J19") (pin "2-A4") (pinfunction "MS_2-A4") (pintype "passive"))
    )
    (net (code "337") (name "unconnected-(J19CN-MS-Pad2-A5)") (class "Default")
      (node (ref "J19") (pin "2-A5") (pinfunction "MS_2-A5") (pintype "passive"))
    )
    (net (code "338") (name "unconnected-(J19CO-MS-Pad2-A6)") (class "Default")
      (node (ref "J19") (pin "2-A6") (pinfunction "MS_2-A6") (pintype "passive"))
    )
    (net (code "339") (name "unconnected-(J19CP-MS-Pad2-A7)") (class "Default")
      (node (ref "J19") (pin "2-A7") (pinfunction "MS_2-A7") (pintype "passive"))
    )
    (net (code "340") (name "unconnected-(J19CQ-MS-Pad2-A8)") (class "Default")
      (node (ref "J19") (pin "2-A8") (pinfunction "MS_2-A8") (pintype "passive"))
    )
    (net (code "341") (name "unconnected-(J19CS-MSV-Pad2-C1)") (class "Default")
      (node (ref "J19") (pin "2-C1") (pinfunction "MSV_2-C1") (pintype "passive"))
    )
    (net (code "342") (name "unconnected-(J19CT-MS-Pad2-C10)") (class "Default")
      (node (ref "J19") (pin "2-C10") (pinfunction "MS_2-C10") (pintype "passive"))
    )
    (net (code "343") (name "unconnected-(J19CU-MS-Pad2-C11)") (class "Default")
      (node (ref "J19") (pin "2-C11") (pinfunction "MS_2-C11") (pintype "passive"))
    )
    (net (code "344") (name "unconnected-(J19CV-MS-Pad2-C12)") (class "Default")
      (node (ref "J19") (pin "2-C12") (pinfunction "MS_2-C12") (pintype "passive"))
    )
    (net (code "345") (name "unconnected-(J19CW-MS-Pad2-C13)") (class "Default")
      (node (ref "J19") (pin "2-C13") (pinfunction "MS_2-C13") (pintype "passive"))
    )
    (net (code "346") (name "unconnected-(J19CX-MS-Pad2-C14)") (class "Default")
      (node (ref "J19") (pin "2-C14") (pinfunction "MS_2-C14") (pintype "passive"))
    )
    (net (code "347") (name "unconnected-(J19CY-MS-Pad2-C15)") (class "Default")
      (node (ref "J19") (pin "2-C15") (pinfunction "MS_2-C15") (pintype "passive"))
    )
    (net (code "348") (name "unconnected-(J19CZ-MS-Pad2-C16)") (class "Default")
      (node (ref "J19") (pin "2-C16") (pinfunction "MS_2-C16") (pintype "passive"))
    )
    (net (code "349") (name "unconnected-(J19D-MS-Pad1-A12)") (class "Default")
      (node (ref "J19") (pin "1-A12") (pinfunction "MS_1-A12") (pintype "passive"))
    )
    (net (code "350") (name "unconnected-(J19DA-MS-Pad2-C17)") (class "Default")
      (node (ref "J19") (pin "2-C17") (pinfunction "MS_2-C17") (pintype "passive"))
    )
    (net (code "351") (name "unconnected-(J19DB-MS-Pad2-C18)") (class "Default")
      (node (ref "J19") (pin "2-C18") (pinfunction "MS_2-C18") (pintype "passive"))
    )
    (net (code "352") (name "unconnected-(J19DC-MS-Pad2-C19)") (class "Default")
      (node (ref "J19") (pin "2-C19") (pinfunction "MS_2-C19") (pintype "passive"))
    )
    (net (code "353") (name "unconnected-(J19DD-MS-Pad2-C2)") (class "Default")
      (node (ref "J19") (pin "2-C2") (pinfunction "MS_2-C2") (pintype "passive"))
    )
    (net (code "354") (name "unconnected-(J19DE-MS-Pad2-C20)") (class "Default")
      (node (ref "J19") (pin "2-C20") (pinfunction "MS_2-C20") (pintype "passive"))
    )
    (net (code "355") (name "unconnected-(J19DF-MS-Pad2-C21)") (class "Default")
      (node (ref "J19") (pin "2-C21") (pinfunction "MS_2-C21") (pintype "passive"))
    )
    (net (code "356") (name "unconnected-(J19DG-MS-Pad2-C22)") (class "Default")
      (node (ref "J19") (pin "2-C22") (pinfunction "MS_2-C22") (pintype "passive"))
    )
    (net (code "357") (name "unconnected-(J19DH-MS-Pad2-C23)") (class "Default")
      (node (ref "J19") (pin "2-C23") (pinfunction "MS_2-C23") (pintype "passive"))
    )
    (net (code "358") (name "unconnected-(J19DI-MS-Pad2-C24)") (class "Default")
      (node (ref "J19") (pin "2-C24") (pinfunction "MS_2-C24") (pintype "passive"))
    )
    (net (code "359") (name "unconnected-(J19DJ-MS-Pad2-C25)") (class "Default")
      (node (ref "J19") (pin "2-C25") (pinfunction "MS_2-C25") (pintype "passive"))
    )
    (net (code "360") (name "unconnected-(J19DK-MS-Pad2-C26)") (class "Default")
      (node (ref "J19") (pin "2-C26") (pinfunction "MS_2-C26") (pintype "passive"))
    )
    (net (code "361") (name "unconnected-(J19DL-MS-Pad2-C27)") (class "Default")
      (node (ref "J19") (pin "2-C27") (pinfunction "MS_2-C27") (pintype "passive"))
    )
    (net (code "362") (name "unconnected-(J19DM-MS-Pad2-C28)") (class "Default")
      (node (ref "J19") (pin "2-C28") (pinfunction "MS_2-C28") (pintype "passive"))
    )
    (net (code "363") (name "unconnected-(J19DN-MS-Pad2-C29)") (class "Default")
      (node (ref "J19") (pin "2-C29") (pinfunction "MS_2-C29") (pintype "passive"))
    )
    (net (code "364") (name "unconnected-(J19DO-MS-Pad2-C3)") (class "Default")
      (node (ref "J19") (pin "2-C3") (pinfunction "MS_2-C3") (pintype "passive"))
    )
    (net (code "365") (name "unconnected-(J19DP-MS-Pad2-C30)") (class "Default")
      (node (ref "J19") (pin "2-C30") (pinfunction "MS_2-C30") (pintype "passive"))
    )
    (net (code "366") (name "unconnected-(J19DQ-MS-Pad2-C31)") (class "Default")
      (node (ref "J19") (pin "2-C31") (pinfunction "MS_2-C31") (pintype "passive"))
    )
    (net (code "367") (name "unconnected-(J19DS-MS-Pad2-C4)") (class "Default")
      (node (ref "J19") (pin "2-C4") (pinfunction "MS_2-C4") (pintype "passive"))
    )
    (net (code "368") (name "unconnected-(J19DT-MS-Pad2-C5)") (class "Default")
      (node (ref "J19") (pin "2-C5") (pinfunction "MS_2-C5") (pintype "passive"))
    )
    (net (code "369") (name "unconnected-(J19DU-MS-Pad2-C6)") (class "Default")
      (node (ref "J19") (pin "2-C6") (pinfunction "MS_2-C6") (pintype "passive"))
    )
    (net (code "370") (name "unconnected-(J19DV-MS-Pad2-C7)") (class "Default")
      (node (ref "J19") (pin "2-C7") (pinfunction "MS_2-C7") (pintype "passive"))
    )
    (net (code "371") (name "unconnected-(J19DW-MS-Pad2-C8)") (class "Default")
      (node (ref "J19") (pin "2-C8") (pinfunction "MS_2-C8") (pintype "passive"))
    )
    (net (code "372") (name "unconnected-(J19E-MS-Pad1-A13)") (class "Default")
      (node (ref "J19") (pin "1-A13") (pinfunction "MS_1-A13") (pintype "passive"))
    )
    (net (code "373") (name "unconnected-(J19F-MS-Pad1-A14)") (class "Default")
      (node (ref "J19") (pin "1-A14") (pinfunction "MS_1-A14") (pintype "passive"))
    )
    (net (code "374") (name "unconnected-(J19G-MS-Pad1-A15)") (class "Default")
      (node (ref "J19") (pin "1-A15") (pinfunction "MS_1-A15") (pintype "passive"))
    )
    (net (code "375") (name "unconnected-(J19H-MS-Pad1-A16)") (class "Default")
      (node (ref "J19") (pin "1-A16") (pinfunction "MS_1-A16") (pintype "passive"))
    )
    (net (code "376") (name "unconnected-(J19I-MS-Pad1-A17)") (class "Default")
      (node (ref "J19") (pin "1-A17") (pinfunction "MS_1-A17") (pintype "passive"))
    )
    (net (code "377") (name "unconnected-(J19J-MS-Pad1-A18)") (class "Default")
      (node (ref "J19") (pin "1-A18") (pinfunction "MS_1-A18") (pintype "passive"))
    )
    (net (code "378") (name "unconnected-(J19K-MS-Pad1-A19)") (class "Default")
      (node (ref "J19") (pin "1-A19") (pinfunction "MS_1-A19") (pintype "passive"))
    )
    (net (code "379") (name "unconnected-(J19L-MS-Pad1-A2)") (class "Default")
      (node (ref "J19") (pin "1-A2") (pinfunction "MS_1-A2") (pintype "passive"))
    )
    (net (code "380") (name "unconnected-(J19M-MS-Pad1-A20)") (class "Default")
      (node (ref "J19") (pin "1-A20") (pinfunction "MS_1-A20") (pintype "passive"))
    )
    (net (code "381") (name "unconnected-(J19N-MS-Pad1-A21)") (class "Default")
      (node (ref "J19") (pin "1-A21") (pinfunction "MS_1-A21") (pintype "passive"))
    )
    (net (code "382") (name "unconnected-(J19O-MS-Pad1-A22)") (class "Default")
      (node (ref "J19") (pin "1-A22") (pinfunction "MS_1-A22") (pintype "passive"))
    )
    (net (code "383") (name "unconnected-(J19P-MS-Pad1-A23)") (class "Default")
      (node (ref "J19") (pin "1-A23") (pinfunction "MS_1-A23") (pintype "passive"))
    )
    (net (code "384") (name "unconnected-(J19Q-MS-Pad1-A24)") (class "Default")
      (node (ref "J19") (pin "1-A24") (pinfunction "MS_1-A24") (pintype "passive"))
    )
    (net (code "385") (name "unconnected-(J19R-MS-Pad1-A25)") (class "Default")
      (node (ref "J19") (pin "1-A25") (pinfunction "MS_1-A25") (pintype "passive"))
    )
    (net (code "386") (name "unconnected-(J19S-MS-Pad1-A26)") (class "Default")
      (node (ref "J19") (pin "1-A26") (pinfunction "MS_1-A26") (pintype "passive"))
    )
    (net (code "387") (name "unconnected-(J19T-MS-Pad1-A27)") (class "Default")
      (node (ref "J19") (pin "1-A27") (pinfunction "MS_1-A27") (pintype "passive"))
    )
    (net (code "388") (name "unconnected-(J19U-MS-Pad1-A28)") (class "Default")
      (node (ref "J19") (pin "1-A28") (pinfunction "MS_1-A28") (pintype "passive"))
    )
    (net (code "389") (name "unconnected-(J19V-MS-Pad1-A29)") (class "Default")
      (node (ref "J19") (pin "1-A29") (pinfunction "MS_1-A29") (pintype "passive"))
    )
    (net (code "390") (name "unconnected-(J19W-MS-Pad1-A3)") (class "Default")
      (node (ref "J19") (pin "1-A3") (pinfunction "MS_1-A3") (pintype "passive"))
    )
    (net (code "391") (name "unconnected-(J19X-MS-Pad1-A30)") (class "Default")
      (node (ref "J19") (pin "1-A30") (pinfunction "MS_1-A30") (pintype "passive"))
    )
    (net (code "392") (name "unconnected-(J19Y-MS-Pad1-A31)") (class "Default")
      (node (ref "J19") (pin "1-A31") (pinfunction "MS_1-A31") (pintype "passive"))
    )
  )
)
